# LED_PD_LKW_WH_3000030.net
KiCad netlist of a schematic drawn in Altium Designer
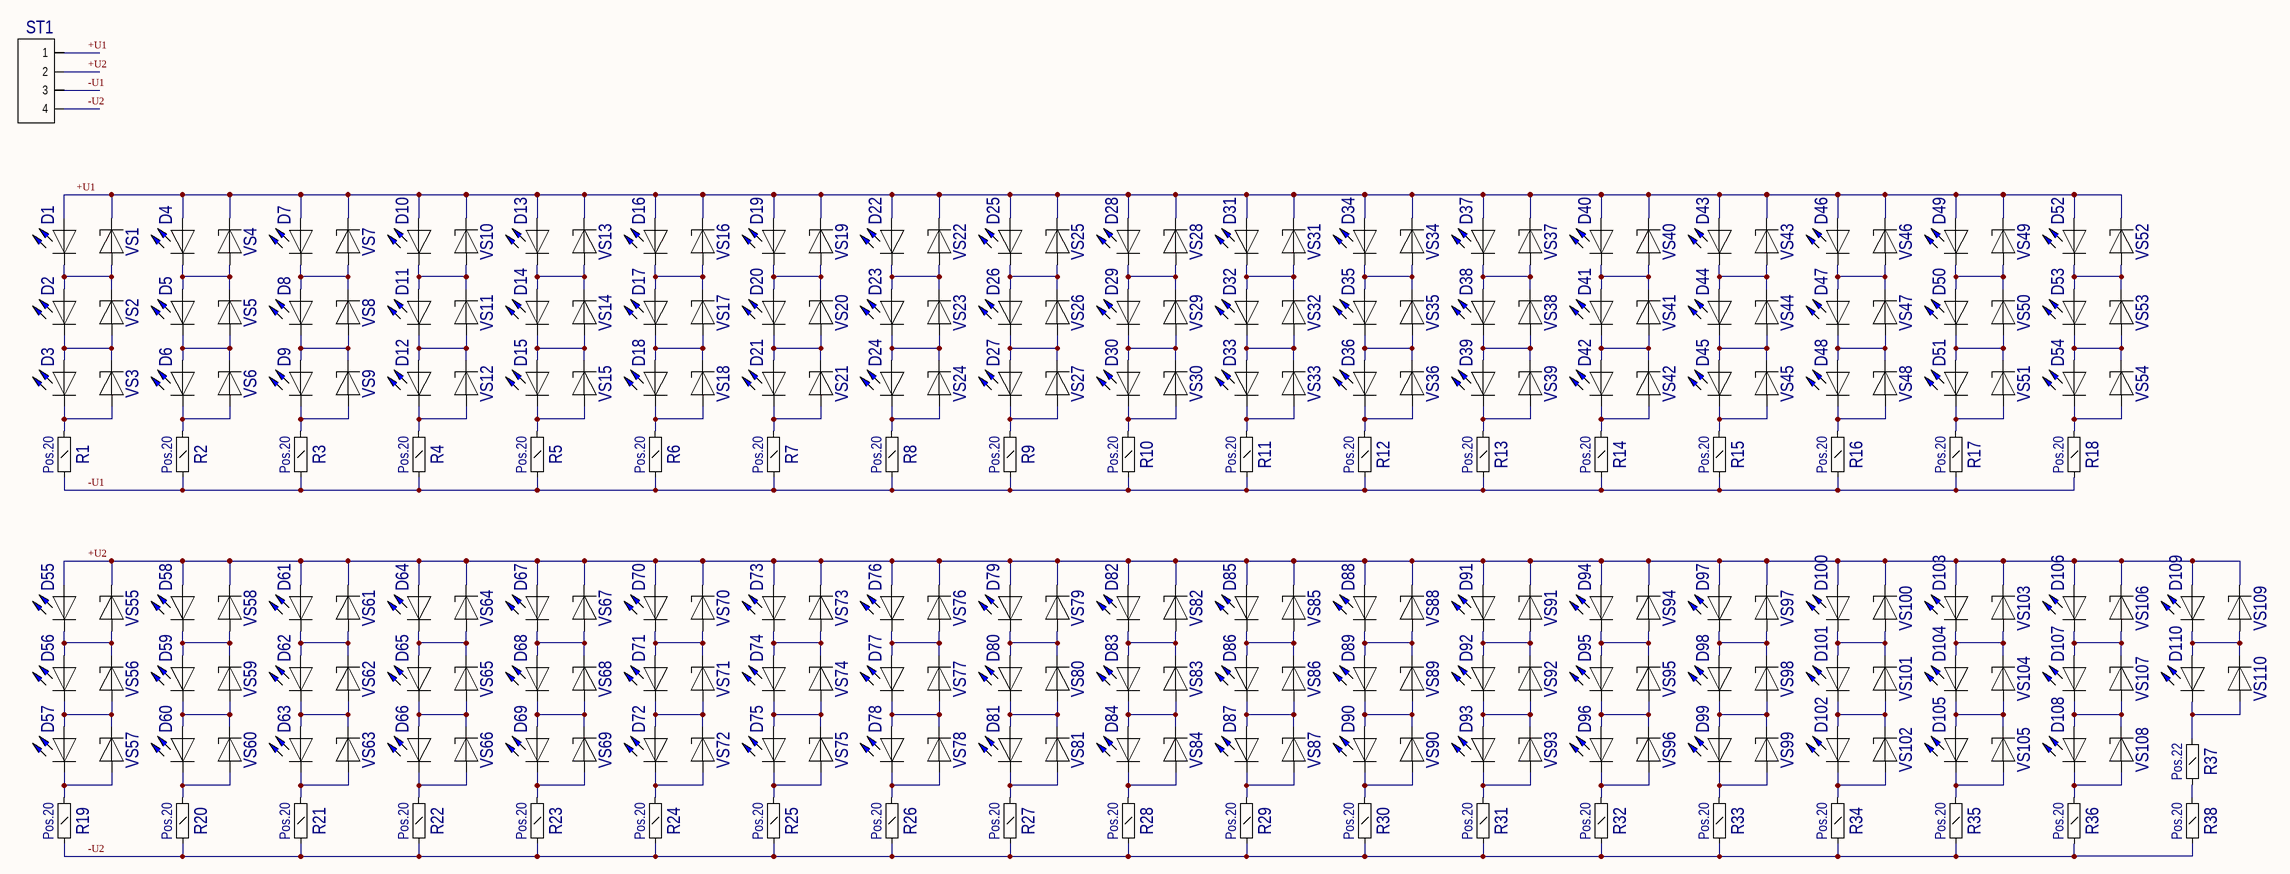
[diagram p0: LED PD LKW WH 3000030 (4F00221L_7P00491A).SchDoc]

(export (version "E")
  (design (tool "Eeschema 10.0.6"))
  (components
    (comp (ref "D1")
      (value "T66G_4")
      (footprint "T66G_4")
      (description "{Description}")
      (libsource (lib "30000137_3LED") (part "T66G_4"))
    )
    (comp (ref "D2")
      (value "T66G_4")
      (footprint "T66G_4")
      (description "{Description}")
      (libsource (lib "30000137_3LED") (part "T66G_4"))
    )
    (comp (ref "D3")
      (value "T66G_4")
      (footprint "T66G_4")
      (description "{Description}")
      (libsource (lib "30000137_3LED") (part "T66G_4"))
    )
    (comp (ref "D4")
      (value "T66G_4")
      (footprint "T66G_4")
      (description "{Description}")
      (libsource (lib "30000137_3LED") (part "T66G_4"))
    )
    (comp (ref "D5")
      (value "T66G_4")
      (footprint "T66G_4")
      (description "{Description}")
      (libsource (lib "30000137_3LED") (part "T66G_4"))
    )
    (comp (ref "D6")
      (value "T66G_4")
      (footprint "T66G_4")
      (description "{Description}")
      (libsource (lib "30000137_3LED") (part "T66G_4"))
    )
    (comp (ref "D7")
      (value "T66G_4")
      (footprint "T66G_4")
      (description "{Description}")
      (libsource (lib "30000137_3LED") (part "T66G_4"))
    )
    (comp (ref "D8")
      (value "T66G_4")
      (footprint "T66G_4")
      (description "{Description}")
      (libsource (lib "30000137_3LED") (part "T66G_4"))
    )
    (comp (ref "D9")
      (value "T66G_4")
      (footprint "T66G_4")
      (description "{Description}")
      (libsource (lib "30000137_3LED") (part "T66G_4"))
    )
    (comp (ref "D10")
      (value "T66G_4")
      (footprint "T66G_4")
      (description "{Description}")
      (libsource (lib "30000137_3LED") (part "T66G_4"))
    )
    (comp (ref "D11")
      (value "T66G_4")
      (footprint "T66G_4")
      (description "{Description}")
      (libsource (lib "30000137_3LED") (part "T66G_4"))
    )
    (comp (ref "D12")
      (value "T66G_4")
      (footprint "T66G_4")
      (description "{Description}")
      (libsource (lib "30000137_3LED") (part "T66G_4"))
    )
    (comp (ref "D13")
      (value "T66G_4")
      (footprint "T66G_4")
      (description "{Description}")
      (libsource (lib "30000137_3LED") (part "T66G_4"))
    )
    (comp (ref "D14")
      (value "T66G_4")
      (footprint "T66G_4")
      (description "{Description}")
      (libsource (lib "30000137_3LED") (part "T66G_4"))
    )
    (comp (ref "D15")
      (value "T66G_4")
      (footprint "T66G_4")
      (description "{Description}")
      (libsource (lib "30000137_3LED") (part "T66G_4"))
    )
    (comp (ref "D16")
      (value "T66G_4")
      (footprint "T66G_4")
      (description "{Description}")
      (libsource (lib "30000137_3LED") (part "T66G_4"))
    )
    (comp (ref "D17")
      (value "T66G_4")
      (footprint "T66G_4")
      (description "{Description}")
      (libsource (lib "30000137_3LED") (part "T66G_4"))
    )
    (comp (ref "D18")
      (value "T66G_4")
      (footprint "T66G_4")
      (description "{Description}")
      (libsource (lib "30000137_3LED") (part "T66G_4"))
    )
    (comp (ref "D19")
      (value "T66G_4")
      (footprint "T66G_4")
      (description "{Description}")
      (libsource (lib "30000137_3LED") (part "T66G_4"))
    )
    (comp (ref "D20")
      (value "T66G_4")
      (footprint "T66G_4")
      (description "{Description}")
      (libsource (lib "30000137_3LED") (part "T66G_4"))
    )
    (comp (ref "D21")
      (value "T66G_4")
      (footprint "T66G_4")
      (description "{Description}")
      (libsource (lib "30000137_3LED") (part "T66G_4"))
    )
    (comp (ref "D22")
      (value "T66G_4")
      (footprint "T66G_4")
      (description "{Description}")
      (libsource (lib "30000137_3LED") (part "T66G_4"))
    )
    (comp (ref "D23")
      (value "T66G_4")
      (footprint "T66G_4")
      (description "{Description}")
      (libsource (lib "30000137_3LED") (part "T66G_4"))
    )
    (comp (ref "D24")
      (value "T66G_4")
      (footprint "T66G_4")
      (description "{Description}")
      (libsource (lib "30000137_3LED") (part "T66G_4"))
    )
    (comp (ref "D25")
      (value "T66G_4")
      (footprint "T66G_4")
      (description "{Description}")
      (libsource (lib "30000137_3LED") (part "T66G_4"))
    )
    (comp (ref "D26")
      (value "T66G_4")
      (footprint "T66G_4")
      (description "{Description}")
      (libsource (lib "30000137_3LED") (part "T66G_4"))
    )
    (comp (ref "D27")
      (value "T66G_4")
      (footprint "T66G_4")
      (description "{Description}")
      (libsource (lib "30000137_3LED") (part "T66G_4"))
    )
    (comp (ref "D28")
      (value "T66G_4")
      (footprint "T66G_4")
      (description "{Description}")
      (libsource (lib "30000137_3LED") (part "T66G_4"))
    )
    (comp (ref "D29")
      (value "T66G_4")
      (footprint "T66G_4")
      (description "{Description}")
      (libsource (lib "30000137_3LED") (part "T66G_4"))
    )
    (comp (ref "D30")
      (value "T66G_4")
      (footprint "T66G_4")
      (description "{Description}")
      (libsource (lib "30000137_3LED") (part "T66G_4"))
    )
    (comp (ref "D31")
      (value "T66G_4")
      (footprint "T66G_4")
      (description "{Description}")
      (libsource (lib "30000137_3LED") (part "T66G_4"))
    )
    (comp (ref "D32")
      (value "T66G_4")
      (footprint "T66G_4")
      (description "{Description}")
      (libsource (lib "30000137_3LED") (part "T66G_4"))
    )
    (comp (ref "D33")
      (value "T66G_4")
      (footprint "T66G_4")
      (description "{Description}")
      (libsource (lib "30000137_3LED") (part "T66G_4"))
    )
    (comp (ref "D34")
      (value "T66G_4")
      (footprint "T66G_4")
      (description "{Description}")
      (libsource (lib "30000137_3LED") (part "T66G_4"))
    )
    (comp (ref "D35")
      (value "T66G_4")
      (footprint "T66G_4")
      (description "{Description}")
      (libsource (lib "30000137_3LED") (part "T66G_4"))
    )
    (comp (ref "D36")
      (value "T66G_4")
      (footprint "T66G_4")
      (description "{Description}")
      (libsource (lib "30000137_3LED") (part "T66G_4"))
    )
    (comp (ref "D37")
      (value "T66G_4")
      (footprint "T66G_4")
      (description "{Description}")
      (libsource (lib "30000137_3LED") (part "T66G_4"))
    )
    (comp (ref "D38")
      (value "T66G_4")
      (footprint "T66G_4")
      (description "{Description}")
      (libsource (lib "30000137_3LED") (part "T66G_4"))
    )
    (comp (ref "D39")
      (value "T66G_4")
      (footprint "T66G_4")
      (description "{Description}")
      (libsource (lib "30000137_3LED") (part "T66G_4"))
    )
    (comp (ref "D40")
      (value "T66G_4")
      (footprint "T66G_4")
      (description "{Description}")
      (libsource (lib "30000137_3LED") (part "T66G_4"))
    )
    (comp (ref "D41")
      (value "T66G_4")
      (footprint "T66G_4")
      (description "{Description}")
      (libsource (lib "30000137_3LED") (part "T66G_4"))
    )
    (comp (ref "D42")
      (value "T66G_4")
      (footprint "T66G_4")
      (description "{Description}")
      (libsource (lib "30000137_3LED") (part "T66G_4"))
    )
    (comp (ref "D43")
      (value "T66G_4")
      (footprint "T66G_4")
      (description "{Description}")
      (libsource (lib "30000137_3LED") (part "T66G_4"))
    )
    (comp (ref "D44")
      (value "T66G_4")
      (footprint "T66G_4")
      (description "{Description}")
      (libsource (lib "30000137_3LED") (part "T66G_4"))
    )
    (comp (ref "D45")
      (value "T66G_4")
      (footprint "T66G_4")
      (description "{Description}")
      (libsource (lib "30000137_3LED") (part "T66G_4"))
    )
    (comp (ref "D46")
      (value "T66G_4")
      (footprint "T66G_4")
      (description "{Description}")
      (libsource (lib "30000137_3LED") (part "T66G_4"))
    )
    (comp (ref "D47")
      (value "T66G_4")
      (footprint "T66G_4")
      (description "{Description}")
      (libsource (lib "30000137_3LED") (part "T66G_4"))
    )
    (comp (ref "D48")
      (value "T66G_4")
      (footprint "T66G_4")
      (description "{Description}")
      (libsource (lib "30000137_3LED") (part "T66G_4"))
    )
    (comp (ref "D49")
      (value "T66G_4")
      (footprint "T66G_4")
      (description "{Description}")
      (libsource (lib "30000137_3LED") (part "T66G_4"))
    )
    (comp (ref "D50")
      (value "T66G_4")
      (footprint "T66G_4")
      (description "{Description}")
      (libsource (lib "30000137_3LED") (part "T66G_4"))
    )
    (comp (ref "D51")
      (value "T66G_4")
      (footprint "T66G_4")
      (description "{Description}")
      (libsource (lib "30000137_3LED") (part "T66G_4"))
    )
    (comp (ref "D52")
      (value "T66G_4")
      (footprint "T66G_4")
      (description "{Description}")
      (libsource (lib "30000137_3LED") (part "T66G_4"))
    )
    (comp (ref "D53")
      (value "T66G_4")
      (footprint "T66G_4")
      (description "{Description}")
      (libsource (lib "30000137_3LED") (part "T66G_4"))
    )
    (comp (ref "D54")
      (value "T66G_4")
      (footprint "T66G_4")
      (description "{Description}")
      (libsource (lib "30000137_3LED") (part "T66G_4"))
    )
    (comp (ref "D55")
      (value "T66G_4")
      (footprint "T66G_4")
      (description "{Description}")
      (libsource (lib "30000137_3LED") (part "T66G_4"))
    )
    (comp (ref "D56")
      (value "T66G_4")
      (footprint "T66G_4")
      (description "{Description}")
      (libsource (lib "30000137_3LED") (part "T66G_4"))
    )
    (comp (ref "D57")
      (value "T66G_4")
      (footprint "T66G_4")
      (description "{Description}")
      (libsource (lib "30000137_3LED") (part "T66G_4"))
    )
    (comp (ref "D58")
      (value "T66G_4")
      (footprint "T66G_4")
      (description "{Description}")
      (libsource (lib "30000137_3LED") (part "T66G_4"))
    )
    (comp (ref "D59")
      (value "T66G_4")
      (footprint "T66G_4")
      (description "{Description}")
      (libsource (lib "30000137_3LED") (part "T66G_4"))
    )
    (comp (ref "D60")
      (value "T66G_4")
      (footprint "T66G_4")
      (description "{Description}")
      (libsource (lib "30000137_3LED") (part "T66G_4"))
    )
    (comp (ref "D61")
      (value "T66G_4")
      (footprint "T66G_4")
      (description "{Description}")
      (libsource (lib "30000137_3LED") (part "T66G_4"))
    )
    (comp (ref "D62")
      (value "T66G_4")
      (footprint "T66G_4")
      (description "{Description}")
      (libsource (lib "30000137_3LED") (part "T66G_4"))
    )
    (comp (ref "D63")
      (value "T66G_4")
      (footprint "T66G_4")
      (description "{Description}")
      (libsource (lib "30000137_3LED") (part "T66G_4"))
    )
    (comp (ref "D64")
      (value "T66G_4")
      (footprint "T66G_4")
      (description "{Description}")
      (libsource (lib "30000137_3LED") (part "T66G_4"))
    )
    (comp (ref "D65")
      (value "T66G_4")
      (footprint "T66G_4")
      (description "{Description}")
      (libsource (lib "30000137_3LED") (part "T66G_4"))
    )
    (comp (ref "D66")
      (value "T66G_4")
      (footprint "T66G_4")
      (description "{Description}")
      (libsource (lib "30000137_3LED") (part "T66G_4"))
    )
    (comp (ref "D67")
      (value "T66G_4")
      (footprint "T66G_4")
      (description "{Description}")
      (libsource (lib "30000137_3LED") (part "T66G_4"))
    )
    (comp (ref "D68")
      (value "T66G_4")
      (footprint "T66G_4")
      (description "{Description}")
      (libsource (lib "30000137_3LED") (part "T66G_4"))
    )
    (comp (ref "D69")
      (value "T66G_4")
      (footprint "T66G_4")
      (description "{Description}")
      (libsource (lib "30000137_3LED") (part "T66G_4"))
    )
    (comp (ref "D70")
      (value "T66G_4")
      (footprint "T66G_4")
      (description "{Description}")
      (libsource (lib "30000137_3LED") (part "T66G_4"))
    )
    (comp (ref "D71")
      (value "T66G_4")
      (footprint "T66G_4")
      (description "{Description}")
      (libsource (lib "30000137_3LED") (part "T66G_4"))
    )
    (comp (ref "D72")
      (value "T66G_4")
      (footprint "T66G_4")
      (description "{Description}")
      (libsource (lib "30000137_3LED") (part "T66G_4"))
    )
    (comp (ref "D73")
      (value "T66G_4")
      (footprint "T66G_4")
      (description "{Description}")
      (libsource (lib "30000137_3LED") (part "T66G_4"))
    )
    (comp (ref "D74")
      (value "T66G_4")
      (footprint "T66G_4")
      (description "{Description}")
      (libsource (lib "30000137_3LED") (part "T66G_4"))
    )
    (comp (ref "D75")
      (value "T66G_4")
      (footprint "T66G_4")
      (description "{Description}")
      (libsource (lib "30000137_3LED") (part "T66G_4"))
    )
    (comp (ref "D76")
      (value "T66G_4")
      (footprint "T66G_4")
      (description "{Description}")
      (libsource (lib "30000137_3LED") (part "T66G_4"))
    )
    (comp (ref "D77")
      (value "T66G_4")
      (footprint "T66G_4")
      (description "{Description}")
      (libsource (lib "30000137_3LED") (part "T66G_4"))
    )
    (comp (ref "D78")
      (value "T66G_4")
      (footprint "T66G_4")
      (description "{Description}")
      (libsource (lib "30000137_3LED") (part "T66G_4"))
    )
    (comp (ref "D79")
      (value "T66G_4")
      (footprint "T66G_4")
      (description "{Description}")
      (libsource (lib "30000137_3LED") (part "T66G_4"))
    )
    (comp (ref "D80")
      (value "T66G_4")
      (footprint "T66G_4")
      (description "{Description}")
      (libsource (lib "30000137_3LED") (part "T66G_4"))
    )
    (comp (ref "D81")
      (value "T66G_4")
      (footprint "T66G_4")
      (description "{Description}")
      (libsource (lib "30000137_3LED") (part "T66G_4"))
    )
    (comp (ref "D82")
      (value "T66G_4")
      (footprint "T66G_4")
      (description "{Description}")
      (libsource (lib "30000137_3LED") (part "T66G_4"))
    )
    (comp (ref "D83")
      (value "T66G_4")
      (footprint "T66G_4")
      (description "{Description}")
      (libsource (lib "30000137_3LED") (part "T66G_4"))
    )
    (comp (ref "D84")
      (value "T66G_4")
      (footprint "T66G_4")
      (description "{Description}")
      (libsource (lib "30000137_3LED") (part "T66G_4"))
    )
    (comp (ref "D85")
      (value "T66G_4")
      (footprint "T66G_4")
      (description "{Description}")
      (libsource (lib "30000137_3LED") (part "T66G_4"))
    )
    (comp (ref "D86")
      (value "T66G_4")
      (footprint "T66G_4")
      (description "{Description}")
      (libsource (lib "30000137_3LED") (part "T66G_4"))
    )
    (comp (ref "D87")
      (value "T66G_4")
      (footprint "T66G_4")
      (description "{Description}")
      (libsource (lib "30000137_3LED") (part "T66G_4"))
    )
    (comp (ref "D88")
      (value "T66G_4")
      (footprint "T66G_4")
      (description "{Description}")
      (libsource (lib "30000137_3LED") (part "T66G_4"))
    )
    (comp (ref "D89")
      (value "T66G_4")
      (footprint "T66G_4")
      (description "{Description}")
      (libsource (lib "30000137_3LED") (part "T66G_4"))
    )
    (comp (ref "D90")
      (value "T66G_4")
      (footprint "T66G_4")
      (description "{Description}")
      (libsource (lib "30000137_3LED") (part "T66G_4"))
    )
    (comp (ref "D91")
      (value "T66G_4")
      (footprint "T66G_4")
      (description "{Description}")
      (libsource (lib "30000137_3LED") (part "T66G_4"))
    )
    (comp (ref "D92")
      (value "T66G_4")
      (footprint "T66G_4")
      (description "{Description}")
      (libsource (lib "30000137_3LED") (part "T66G_4"))
    )
    (comp (ref "D93")
      (value "T66G_4")
      (footprint "T66G_4")
      (description "{Description}")
      (libsource (lib "30000137_3LED") (part "T66G_4"))
    )
    (comp (ref "D94")
      (value "T66G_4")
      (footprint "T66G_4")
      (description "{Description}")
      (libsource (lib "30000137_3LED") (part "T66G_4"))
    )
    (comp (ref "D95")
      (value "T66G_4")
      (footprint "T66G_4")
      (description "{Description}")
      (libsource (lib "30000137_3LED") (part "T66G_4"))
    )
    (comp (ref "D96")
      (value "T66G_4")
      (footprint "T66G_4")
      (description "{Description}")
      (libsource (lib "30000137_3LED") (part "T66G_4"))
    )
    (comp (ref "D97")
      (value "T66G_4")
      (footprint "T66G_4")
      (description "{Description}")
      (libsource (lib "30000137_3LED") (part "T66G_4"))
    )
    (comp (ref "D98")
      (value "T66G_4")
      (footprint "T66G_4")
      (description "{Description}")
      (libsource (lib "30000137_3LED") (part "T66G_4"))
    )
    (comp (ref "D99")
      (value "T66G_4")
      (footprint "T66G_4")
      (description "{Description}")
      (libsource (lib "30000137_3LED") (part "T66G_4"))
    )
    (comp (ref "D100")
      (value "T66G_4")
      (footprint "T66G_4")
      (description "{Description}")
      (libsource (lib "30000137_3LED") (part "T66G_4"))
    )
    (comp (ref "D101")
      (value "T66G_4")
      (footprint "T66G_4")
      (description "{Description}")
      (libsource (lib "30000137_3LED") (part "T66G_4"))
    )
    (comp (ref "D102")
      (value "T66G_4")
      (footprint "T66G_4")
      (description "{Description}")
      (libsource (lib "30000137_3LED") (part "T66G_4"))
    )
    (comp (ref "D103")
      (value "T66G_4")
      (footprint "T66G_4")
      (description "{Description}")
      (libsource (lib "30000137_3LED") (part "T66G_4"))
    )
    (comp (ref "D104")
      (value "T66G_4")
      (footprint "T66G_4")
      (description "{Description}")
      (libsource (lib "30000137_3LED") (part "T66G_4"))
    )
    (comp (ref "D105")
      (value "T66G_4")
      (footprint "T66G_4")
      (description "{Description}")
      (libsource (lib "30000137_3LED") (part "T66G_4"))
    )
    (comp (ref "D106")
      (value "T66G_4")
      (footprint "T66G_4")
      (description "{Description}")
      (libsource (lib "30000137_3LED") (part "T66G_4"))
    )
    (comp (ref "D107")
      (value "T66G_4")
      (footprint "T66G_4")
      (description "{Description}")
      (libsource (lib "30000137_3LED") (part "T66G_4"))
    )
    (comp (ref "D108")
      (value "T66G_4")
      (footprint "T66G_4")
      (description "{Description}")
      (libsource (lib "30000137_3LED") (part "T66G_4"))
    )
    (comp (ref "D109")
      (value "T66G_4")
      (footprint "T66G_4")
      (description "{Description}")
      (libsource (lib "30000137_3LED") (part "T66G_4"))
    )
    (comp (ref "D110")
      (value "T66G_4")
      (footprint "T66G_4")
      (description "{Description}")
      (libsource (lib "30000137_3LED") (part "T66G_4"))
    )
    (comp (ref "R1")
      (value "Pos.20")
      (footprint "RC1206S")
      (description "R1206S")
      (libsource (lib "30000137_3LED") (part "R1206S"))
    )
    (comp (ref "R2")
      (value "Pos.20")
      (footprint "RC1206S")
      (description "R1206S")
      (libsource (lib "30000137_3LED") (part "R1206S"))
    )
    (comp (ref "R3")
      (value "Pos.20")
      (footprint "RC1206S")
      (description "R1206S")
      (libsource (lib "30000137_3LED") (part "R1206S"))
    )
    (comp (ref "R4")
      (value "Pos.20")
      (footprint "RC1206S")
      (description "R1206S")
      (libsource (lib "30000137_3LED") (part "R1206S"))
    )
    (comp (ref "R5")
      (value "Pos.20")
      (footprint "RC1206S")
      (description "R1206S")
      (libsource (lib "30000137_3LED") (part "R1206S"))
    )
    (comp (ref "R6")
      (value "Pos.20")
      (footprint "RC1206S")
      (description "R1206S")
      (libsource (lib "30000137_3LED") (part "R1206S"))
    )
    (comp (ref "R7")
      (value "Pos.20")
      (footprint "RC1206S")
      (description "R1206S")
      (libsource (lib "30000137_3LED") (part "R1206S"))
    )
    (comp (ref "R8")
      (value "Pos.20")
      (footprint "RC1206S")
      (description "R1206S")
      (libsource (lib "30000137_3LED") (part "R1206S"))
    )
    (comp (ref "R9")
      (value "Pos.20")
      (footprint "RC1206S")
      (description "R1206S")
      (libsource (lib "30000137_3LED") (part "R1206S"))
    )
    (comp (ref "R10")
      (value "Pos.20")
      (footprint "RC1206S")
      (description "R1206S")
      (libsource (lib "30000137_3LED") (part "R1206S"))
    )
    (comp (ref "R11")
      (value "Pos.20")
      (footprint "RC1206S")
      (description "R1206S")
      (libsource (lib "30000137_3LED") (part "R1206S"))
    )
    (comp (ref "R12")
      (value "Pos.20")
      (footprint "RC1206S")
      (description "R1206S")
      (libsource (lib "30000137_3LED") (part "R1206S"))
    )
    (comp (ref "R13")
      (value "Pos.20")
      (footprint "RC1206S")
      (description "R1206S")
      (libsource (lib "30000137_3LED") (part "R1206S"))
    )
    (comp (ref "R14")
      (value "Pos.20")
      (footprint "RC1206S")
      (description "R1206S")
      (libsource (lib "30000137_3LED") (part "R1206S"))
    )
    (comp (ref "R15")
      (value "Pos.20")
      (footprint "RC1206S")
      (description "R1206S")
      (libsource (lib "30000137_3LED") (part "R1206S"))
    )
    (comp (ref "R16")
      (value "Pos.20")
      (footprint "RC1206S")
      (description "R1206S")
      (libsource (lib "30000137_3LED") (part "R1206S"))
    )
    (comp (ref "R17")
      (value "Pos.20")
      (footprint "RC1206S")
      (description "R1206S")
      (libsource (lib "30000137_3LED") (part "R1206S"))
    )
    (comp (ref "R18")
      (value "Pos.20")
      (footprint "RC1206S")
      (description "R1206S")
      (libsource (lib "30000137_3LED") (part "R1206S"))
    )
    (comp (ref "R19")
      (value "Pos.20")
      (footprint "RC1206S")
      (description "R1206S")
      (libsource (lib "30000137_3LED") (part "R1206S"))
    )
    (comp (ref "R20")
      (value "Pos.20")
      (footprint "RC1206S")
      (description "R1206S")
      (libsource (lib "30000137_3LED") (part "R1206S"))
    )
    (comp (ref "R21")
      (value "Pos.20")
      (footprint "RC1206S")
      (description "R1206S")
      (libsource (lib "30000137_3LED") (part "R1206S"))
    )
    (comp (ref "R22")
      (value "Pos.20")
      (footprint "RC1206S")
      (description "R1206S")
      (libsource (lib "30000137_3LED") (part "R1206S"))
    )
    (comp (ref "R23")
      (value "Pos.20")
      (footprint "RC1206S")
      (description "R1206S")
      (libsource (lib "30000137_3LED") (part "R1206S"))
    )
    (comp (ref "R24")
      (value "Pos.20")
      (footprint "RC1206S")
      (description "R1206S")
      (libsource (lib "30000137_3LED") (part "R1206S"))
    )
    (comp (ref "R25")
      (value "Pos.20")
      (footprint "RC1206S")
      (description "R1206S")
      (libsource (lib "30000137_3LED") (part "R1206S"))
    )
    (comp (ref "R26")
      (value "Pos.20")
      (footprint "RC1206S")
      (description "R1206S")
      (libsource (lib "30000137_3LED") (part "R1206S"))
    )
    (comp (ref "R27")
      (value "Pos.20")
      (footprint "RC1206S")
      (description "R1206S")
      (libsource (lib "30000137_3LED") (part "R1206S"))
    )
    (comp (ref "R28")
      (value "Pos.20")
      (footprint "RC1206S")
      (description "R1206S")
      (libsource (lib "30000137_3LED") (part "R1206S"))
    )
    (comp (ref "R29")
      (value "Pos.20")
      (footprint "RC1206S")
      (description "R1206S")
      (libsource (lib "30000137_3LED") (part "R1206S"))
    )
    (comp (ref "R30")
      (value "Pos.20")
      (footprint "RC1206S")
      (description "R1206S")
      (libsource (lib "30000137_3LED") (part "R1206S"))
    )
    (comp (ref "R31")
      (value "Pos.20")
      (footprint "RC1206S")
      (description "R1206S")
      (libsource (lib "30000137_3LED") (part "R1206S"))
    )
    (comp (ref "R32")
      (value "Pos.20")
      (footprint "RC1206S")
      (description "R1206S")
      (libsource (lib "30000137_3LED") (part "R1206S"))
    )
    (comp (ref "R33")
      (value "Pos.20")
      (footprint "RC1206S")
      (description "R1206S")
      (libsource (lib "30000137_3LED") (part "R1206S"))
    )
    (comp (ref "R34")
      (value "Pos.20")
      (footprint "RC1206S")
      (description "R1206S")
      (libsource (lib "30000137_3LED") (part "R1206S"))
    )
    (comp (ref "R35")
      (value "Pos.20")
      (footprint "RC1206S")
      (description "R1206S")
      (libsource (lib "30000137_3LED") (part "R1206S"))
    )
    (comp (ref "R36")
      (value "Pos.20")
      (footprint "RC1206S")
      (description "R1206S")
      (libsource (lib "30000137_3LED") (part "R1206S"))
    )
    (comp (ref "R37")
      (value "Pos.22")
      (footprint "RC1206S")
      (description "R1206S")
      (libsource (lib "30000137_3LED") (part "R1206S_1"))
    )
    (comp (ref "R38")
      (value "Pos.20")
      (footprint "RC1206S")
      (description "R1206S")
      (libsource (lib "30000137_3LED") (part "R1206S"))
    )
    (comp (ref "ST1") (value "BAND4") (footprint "BAND4") (libsource (lib "30000137_3LED") (part "BAND4")))
    (comp (ref "VS1") (value "BZX84") (footprint "SOT23") (libsource (lib "30000137_3LED") (part "BZX84")))
    (comp (ref "VS2") (value "BZX84") (footprint "SOT23") (libsource (lib "30000137_3LED") (part "BZX84")))
    (comp (ref "VS3") (value "BZX84") (footprint "SOT23") (libsource (lib "30000137_3LED") (part "BZX84")))
    (comp (ref "VS4") (value "BZX84") (footprint "SOT23") (libsource (lib "30000137_3LED") (part "BZX84")))
    (comp (ref "VS5") (value "BZX84") (footprint "SOT23") (libsource (lib "30000137_3LED") (part "BZX84")))
    (comp (ref "VS6") (value "BZX84") (footprint "SOT23") (libsource (lib "30000137_3LED") (part "BZX84")))
    (comp (ref "VS7") (value "BZX84") (footprint "SOT23") (libsource (lib "30000137_3LED") (part "BZX84")))
    (comp (ref "VS8") (value "BZX84") (footprint "SOT23") (libsource (lib "30000137_3LED") (part "BZX84")))
    (comp (ref "VS9") (value "BZX84") (footprint "SOT23") (libsource (lib "30000137_3LED") (part "BZX84")))
    (comp (ref "VS10") (value "BZX84") (footprint "SOT23") (libsource (lib "30000137_3LED") (part "BZX84")))
    (comp (ref "VS11") (value "BZX84") (footprint "SOT23") (libsource (lib "30000137_3LED") (part "BZX84")))
    (comp (ref "VS12") (value "BZX84") (footprint "SOT23") (libsource (lib "30000137_3LED") (part "BZX84")))
    (comp (ref "VS13") (value "BZX84") (footprint "SOT23") (libsource (lib "30000137_3LED") (part "BZX84")))
    (comp (ref "VS14") (value "BZX84") (footprint "SOT23") (libsource (lib "30000137_3LED") (part "BZX84")))
    (comp (ref "VS15") (value "BZX84") (footprint "SOT23") (libsource (lib "30000137_3LED") (part "BZX84")))
    (comp (ref "VS16") (value "BZX84") (footprint "SOT23") (libsource (lib "30000137_3LED") (part "BZX84")))
    (comp (ref "VS17") (value "BZX84") (footprint "SOT23") (libsource (lib "30000137_3LED") (part "BZX84")))
    (comp (ref "VS18") (value "BZX84") (footprint "SOT23") (libsource (lib "30000137_3LED") (part "BZX84")))
    (comp (ref "VS19") (value "BZX84") (footprint "SOT23") (libsource (lib "30000137_3LED") (part "BZX84")))
    (comp (ref "VS20") (value "BZX84") (footprint "SOT23") (libsource (lib "30000137_3LED") (part "BZX84")))
    (comp (ref "VS21") (value "BZX84") (footprint "SOT23") (libsource (lib "30000137_3LED") (part "BZX84")))
    (comp (ref "VS22") (value "BZX84") (footprint "SOT23") (libsource (lib "30000137_3LED") (part "BZX84")))
    (comp (ref "VS23") (value "BZX84") (footprint "SOT23") (libsource (lib "30000137_3LED") (part "BZX84")))
    (comp (ref "VS24") (value "BZX84") (footprint "SOT23") (libsource (lib "30000137_3LED") (part "BZX84")))
    (comp (ref "VS25") (value "BZX84") (footprint "SOT23") (libsource (lib "30000137_3LED") (part "BZX84")))
    (comp (ref "VS26") (value "BZX84") (footprint "SOT23") (libsource (lib "30000137_3LED") (part "BZX84")))
    (comp (ref "VS27") (value "BZX84") (footprint "SOT23") (libsource (lib "30000137_3LED") (part "BZX84")))
    (comp (ref "VS28") (value "BZX84") (footprint "SOT23") (libsource (lib "30000137_3LED") (part "BZX84")))
    (comp (ref "VS29") (value "BZX84") (footprint "SOT23") (libsource (lib "30000137_3LED") (part "BZX84")))
    (comp (ref "VS30") (value "BZX84") (footprint "SOT23") (libsource (lib "30000137_3LED") (part "BZX84")))
    (comp (ref "VS31") (value "BZX84") (footprint "SOT23") (libsource (lib "30000137_3LED") (part "BZX84")))
    (comp (ref "VS32") (value "BZX84") (footprint "SOT23") (libsource (lib "30000137_3LED") (part "BZX84")))
    (comp (ref "VS33") (value "BZX84") (footprint "SOT23") (libsource (lib "30000137_3LED") (part "BZX84")))
    (comp (ref "VS34") (value "BZX84") (footprint "SOT23") (libsource (lib "30000137_3LED") (part "BZX84")))
    (comp (ref "VS35") (value "BZX84") (footprint "SOT23") (libsource (lib "30000137_3LED") (part "BZX84")))
    (comp (ref "VS36") (value "BZX84") (footprint "SOT23") (libsource (lib "30000137_3LED") (part "BZX84")))
    (comp (ref "VS37") (value "BZX84") (footprint "SOT23") (libsource (lib "30000137_3LED") (part "BZX84")))
    (comp (ref "VS38") (value "BZX84") (footprint "SOT23") (libsource (lib "30000137_3LED") (part "BZX84")))
    (comp (ref "VS39") (value "BZX84") (footprint "SOT23") (libsource (lib "30000137_3LED") (part "BZX84")))
    (comp (ref "VS40") (value "BZX84") (footprint "SOT23") (libsource (lib "30000137_3LED") (part "BZX84")))
    (comp (ref "VS41") (value "BZX84") (footprint "SOT23") (libsource (lib "30000137_3LED") (part "BZX84")))
    (comp (ref "VS42") (value "BZX84") (footprint "SOT23") (libsource (lib "30000137_3LED") (part "BZX84")))
    (comp (ref "VS43") (value "BZX84") (footprint "SOT23") (libsource (lib "30000137_3LED") (part "BZX84")))
    (comp (ref "VS44") (value "BZX84") (footprint "SOT23") (libsource (lib "30000137_3LED") (part "BZX84")))
    (comp (ref "VS45") (value "BZX84") (footprint "SOT23") (libsource (lib "30000137_3LED") (part "BZX84")))
    (comp (ref "VS46") (value "BZX84") (footprint "SOT23") (libsource (lib "30000137_3LED") (part "BZX84")))
    (comp (ref "VS47") (value "BZX84") (footprint "SOT23") (libsource (lib "30000137_3LED") (part "BZX84")))
    (comp (ref "VS48") (value "BZX84") (footprint "SOT23") (libsource (lib "30000137_3LED") (part "BZX84")))
    (comp (ref "VS49") (value "BZX84") (footprint "SOT23") (libsource (lib "30000137_3LED") (part "BZX84")))
    (comp (ref "VS50") (value "BZX84") (footprint "SOT23") (libsource (lib "30000137_3LED") (part "BZX84")))
    (comp (ref "VS51") (value "BZX84") (footprint "SOT23") (libsource (lib "30000137_3LED") (part "BZX84")))
    (comp (ref "VS52") (value "BZX84") (footprint "SOT23") (libsource (lib "30000137_3LED") (part "BZX84")))
    (comp (ref "VS53") (value "BZX84") (footprint "SOT23") (libsource (lib "30000137_3LED") (part "BZX84")))
    (comp (ref "VS54") (value "BZX84") (footprint "SOT23") (libsource (lib "30000137_3LED") (part "BZX84")))
    (comp (ref "VS55") (value "BZX84") (footprint "SOT23") (libsource (lib "30000137_3LED") (part "BZX84")))
    (comp (ref "VS56") (value "BZX84") (footprint "SOT23") (libsource (lib "30000137_3LED") (part "BZX84")))
    (comp (ref "VS57") (value "BZX84") (footprint "SOT23") (libsource (lib "30000137_3LED") (part "BZX84")))
    (comp (ref "VS58") (value "BZX84") (footprint "SOT23") (libsource (lib "30000137_3LED") (part "BZX84")))
    (comp (ref "VS59") (value "BZX84") (footprint "SOT23") (libsource (lib "30000137_3LED") (part "BZX84")))
    (comp (ref "VS60") (value "BZX84") (footprint "SOT23") (libsource (lib "30000137_3LED") (part "BZX84")))
    (comp (ref "VS61") (value "BZX84") (footprint "SOT23") (libsource (lib "30000137_3LED") (part "BZX84")))
    (comp (ref "VS62") (value "BZX84") (footprint "SOT23") (libsource (lib "30000137_3LED") (part "BZX84")))
    (comp (ref "VS63") (value "BZX84") (footprint "SOT23") (libsource (lib "30000137_3LED") (part "BZX84")))
    (comp (ref "VS64") (value "BZX84") (footprint "SOT23") (libsource (lib "30000137_3LED") (part "BZX84")))
    (comp (ref "VS65") (value "BZX84") (footprint "SOT23") (libsource (lib "30000137_3LED") (part "BZX84")))
    (comp (ref "VS66") (value "BZX84") (footprint "SOT23") (libsource (lib "30000137_3LED") (part "BZX84")))
    (comp (ref "VS67") (value "BZX84") (footprint "SOT23") (libsource (lib "30000137_3LED") (part "BZX84")))
    (comp (ref "VS68") (value "BZX84") (footprint "SOT23") (libsource (lib "30000137_3LED") (part "BZX84")))
    (comp (ref "VS69") (value "BZX84") (footprint "SOT23") (libsource (lib "30000137_3LED") (part "BZX84")))
    (comp (ref "VS70") (value "BZX84") (footprint "SOT23") (libsource (lib "30000137_3LED") (part "BZX84")))
    (comp (ref "VS71") (value "BZX84") (footprint "SOT23") (libsource (lib "30000137_3LED") (part "BZX84")))
    (comp (ref "VS72") (value "BZX84") (footprint "SOT23") (libsource (lib "30000137_3LED") (part "BZX84")))
    (comp (ref "VS73") (value "BZX84") (footprint "SOT23") (libsource (lib "30000137_3LED") (part "BZX84")))
    (comp (ref "VS74") (value "BZX84") (footprint "SOT23") (libsource (lib "30000137_3LED") (part "BZX84")))
    (comp (ref "VS75") (value "BZX84") (footprint "SOT23") (libsource (lib "30000137_3LED") (part "BZX84")))
    (comp (ref "VS76") (value "BZX84") (footprint "SOT23") (libsource (lib "30000137_3LED") (part "BZX84")))
    (comp (ref "VS77") (value "BZX84") (footprint "SOT23") (libsource (lib "30000137_3LED") (part "BZX84")))
    (comp (ref "VS78") (value "BZX84") (footprint "SOT23") (libsource (lib "30000137_3LED") (part "BZX84")))
    (comp (ref "VS79") (value "BZX84") (footprint "SOT23") (libsource (lib "30000137_3LED") (part "BZX84")))
    (comp (ref "VS80") (value "BZX84") (footprint "SOT23") (libsource (lib "30000137_3LED") (part "BZX84")))
    (comp (ref "VS81") (value "BZX84") (footprint "SOT23") (libsource (lib "30000137_3LED") (part "BZX84")))
    (comp (ref "VS82") (value "BZX84") (footprint "SOT23") (libsource (lib "30000137_3LED") (part "BZX84")))
    (comp (ref "VS83") (value "BZX84") (footprint "SOT23") (libsource (lib "30000137_3LED") (part "BZX84")))
    (comp (ref "VS84") (value "BZX84") (footprint "SOT23") (libsource (lib "30000137_3LED") (part "BZX84")))
    (comp (ref "VS85") (value "BZX84") (footprint "SOT23") (libsource (lib "30000137_3LED") (part "BZX84")))
    (comp (ref "VS86") (value "BZX84") (footprint "SOT23") (libsource (lib "30000137_3LED") (part "BZX84")))
    (comp (ref "VS87") (value "BZX84") (footprint "SOT23") (libsource (lib "30000137_3LED") (part "BZX84")))
    (comp (ref "VS88") (value "BZX84") (footprint "SOT23") (libsource (lib "30000137_3LED") (part "BZX84")))
    (comp (ref "VS89") (value "BZX84") (footprint "SOT23") (libsource (lib "30000137_3LED") (part "BZX84")))
    (comp (ref "VS90") (value "BZX84") (footprint "SOT23") (libsource (lib "30000137_3LED") (part "BZX84")))
    (comp (ref "VS91") (value "BZX84") (footprint "SOT23") (libsource (lib "30000137_3LED") (part "BZX84")))
    (comp (ref "VS92") (value "BZX84") (footprint "SOT23") (libsource (lib "30000137_3LED") (part "BZX84")))
    (comp (ref "VS93") (value "BZX84") (footprint "SOT23") (libsource (lib "30000137_3LED") (part "BZX84")))
    (comp (ref "VS94") (value "BZX84") (footprint "SOT23") (libsource (lib "30000137_3LED") (part "BZX84")))
    (comp (ref "VS95") (value "BZX84") (footprint "SOT23") (libsource (lib "30000137_3LED") (part "BZX84")))
    (comp (ref "VS96") (value "BZX84") (footprint "SOT23") (libsource (lib "30000137_3LED") (part "BZX84")))
    (comp (ref "VS97") (value "BZX84") (footprint "SOT23") (libsource (lib "30000137_3LED") (part "BZX84")))
    (comp (ref "VS98") (value "BZX84") (footprint "SOT23") (libsource (lib "30000137_3LED") (part "BZX84")))
    (comp (ref "VS99") (value "BZX84") (footprint "SOT23") (libsource (lib "30000137_3LED") (part "BZX84")))
    (comp (ref "VS100") (value "BZX84") (footprint "SOT23") (libsource (lib "30000137_3LED") (part "BZX84")))
    (comp (ref "VS101") (value "BZX84") (footprint "SOT23") (libsource (lib "30000137_3LED") (part "BZX84")))
    (comp (ref "VS102") (value "BZX84") (footprint "SOT23") (libsource (lib "30000137_3LED") (part "BZX84")))
    (comp (ref "VS103") (value "BZX84") (footprint "SOT23") (libsource (lib "30000137_3LED") (part "BZX84")))
    (comp (ref "VS104") (value "BZX84") (footprint "SOT23") (libsource (lib "30000137_3LED") (part "BZX84")))
    (comp (ref "VS105") (value "BZX84") (footprint "SOT23") (libsource (lib "30000137_3LED") (part "BZX84")))
    (comp (ref "VS106") (value "BZX84") (footprint "SOT23") (libsource (lib "30000137_3LED") (part "BZX84")))
    (comp (ref "VS107") (value "BZX84") (footprint "SOT23") (libsource (lib "30000137_3LED") (part "BZX84")))
    (comp (ref "VS108") (value "BZX84") (footprint "SOT23") (libsource (lib "30000137_3LED") (part "BZX84")))
    (comp (ref "VS109") (value "BZX84") (footprint "SOT23") (libsource (lib "30000137_3LED") (part "BZX84")))
    (comp (ref "VS110") (value "BZX84") (footprint "SOT23") (libsource (lib "30000137_3LED") (part "BZX84")))
  )
  (nets
    (net (code "1") (name "/+U1") (class "Default")
      (node (ref "D1") (pin "2") (pinfunction "A_2") (pintype "passive"))
      (node (ref "D10") (pin "2") (pinfunction "A_2") (pintype "passive"))
      (node (ref "D13") (pin "2") (pinfunction "A_2") (pintype "passive"))
      (node (ref "D16") (pin "2") (pinfunction "A_2") (pintype "passive"))
      (node (ref "D19") (pin "2") (pinfunction "A_2") (pintype "passive"))
      (node (ref "D22") (pin "2") (pinfunction "A_2") (pintype "passive"))
      (node (ref "D25") (pin "2") (pinfunction "A_2") (pintype "passive"))
      (node (ref "D28") (pin "2") (pinfunction "A_2") (pintype "passive"))
      (node (ref "D31") (pin "2") (pinfunction "A_2") (pintype "passive"))
      (node (ref "D34") (pin "2") (pinfunction "A_2") (pintype "passive"))
      (node (ref "D37") (pin "2") (pinfunction "A_2") (pintype "passive"))
      (node (ref "D4") (pin "2") (pinfunction "A_2") (pintype "passive"))
      (node (ref "D40") (pin "2") (pinfunction "A_2") (pintype "passive"))
      (node (ref "D43") (pin "2") (pinfunction "A_2") (pintype "passive"))
      (node (ref "D46") (pin "2") (pinfunction "A_2") (pintype "passive"))
      (node (ref "D49") (pin "2") (pinfunction "A_2") (pintype "passive"))
      (node (ref "D52") (pin "2") (pinfunction "A_2") (pintype "passive"))
      (node (ref "D7") (pin "2") (pinfunction "A_2") (pintype "passive"))
      (node (ref "ST1") (pin "1") (pinfunction "1_1") (pintype "passive"))
      (node (ref "VS1") (pin "3") (pintype "passive"))
      (node (ref "VS10") (pin "3") (pintype "passive"))
      (node (ref "VS13") (pin "3") (pintype "passive"))
      (node (ref "VS16") (pin "3") (pintype "passive"))
      (node (ref "VS19") (pin "3") (pintype "passive"))
      (node (ref "VS22") (pin "3") (pintype "passive"))
      (node (ref "VS25") (pin "3") (pintype "passive"))
      (node (ref "VS28") (pin "3") (pintype "passive"))
      (node (ref "VS31") (pin "3") (pintype "passive"))
      (node (ref "VS34") (pin "3") (pintype "passive"))
      (node (ref "VS37") (pin "3") (pintype "passive"))
      (node (ref "VS4") (pin "3") (pintype "passive"))
      (node (ref "VS40") (pin "3") (pintype "passive"))
      (node (ref "VS43") (pin "3") (pintype "passive"))
      (node (ref "VS46") (pin "3") (pintype "passive"))
      (node (ref "VS49") (pin "3") (pintype "passive"))
      (node (ref "VS52") (pin "3") (pintype "passive"))
      (node (ref "VS7") (pin "3") (pintype "passive"))
    )
    (net (code "2") (name "/+U2") (class "Default")
      (node (ref "D100") (pin "2") (pinfunction "A_2") (pintype "passive"))
      (node (ref "D103") (pin "2") (pinfunction "A_2") (pintype "passive"))
      (node (ref "D106") (pin "2") (pinfunction "A_2") (pintype "passive"))
      (node (ref "D109") (pin "2") (pinfunction "A_2") (pintype "passive"))
      (node (ref "D55") (pin "2") (pinfunction "A_2") (pintype "passive"))
      (node (ref "D58") (pin "2") (pinfunction "A_2") (pintype "passive"))
      (node (ref "D61") (pin "2") (pinfunction "A_2") (pintype "passive"))
      (node (ref "D64") (pin "2") (pinfunction "A_2") (pintype "passive"))
      (node (ref "D67") (pin "2") (pinfunction "A_2") (pintype "passive"))
      (node (ref "D70") (pin "2") (pinfunction "A_2") (pintype "passive"))
      (node (ref "D73") (pin "2") (pinfunction "A_2") (pintype "passive"))
      (node (ref "D76") (pin "2") (pinfunction "A_2") (pintype "passive"))
      (node (ref "D79") (pin "2") (pinfunction "A_2") (pintype "passive"))
      (node (ref "D82") (pin "2") (pinfunction "A_2") (pintype "passive"))
      (node (ref "D85") (pin "2") (pinfunction "A_2") (pintype "passive"))
      (node (ref "D88") (pin "2") (pinfunction "A_2") (pintype "passive"))
      (node (ref "D91") (pin "2") (pinfunction "A_2") (pintype "passive"))
      (node (ref "D94") (pin "2") (pinfunction "A_2") (pintype "passive"))
      (node (ref "D97") (pin "2") (pinfunction "A_2") (pintype "passive"))
      (node (ref "ST1") (pin "2") (pinfunction "2_2") (pintype "passive"))
      (node (ref "VS100") (pin "3") (pintype "passive"))
      (node (ref "VS103") (pin "3") (pintype "passive"))
      (node (ref "VS106") (pin "3") (pintype "passive"))
      (node (ref "VS109") (pin "3") (pintype "passive"))
      (node (ref "VS55") (pin "3") (pintype "passive"))
      (node (ref "VS58") (pin "3") (pintype "passive"))
      (node (ref "VS61") (pin "3") (pintype "passive"))
      (node (ref "VS64") (pin "3") (pintype "passive"))
      (node (ref "VS67") (pin "3") (pintype "passive"))
      (node (ref "VS70") (pin "3") (pintype "passive"))
      (node (ref "VS73") (pin "3") (pintype "passive"))
      (node (ref "VS76") (pin "3") (pintype "passive"))
      (node (ref "VS79") (pin "3") (pintype "passive"))
      (node (ref "VS82") (pin "3") (pintype "passive"))
      (node (ref "VS85") (pin "3") (pintype "passive"))
      (node (ref "VS88") (pin "3") (pintype "passive"))
      (node (ref "VS91") (pin "3") (pintype "passive"))
      (node (ref "VS94") (pin "3") (pintype "passive"))
      (node (ref "VS97") (pin "3") (pintype "passive"))
    )
    (net (code "3") (name "/-U1") (class "Default")
      (node (ref "R1") (pin "2") (pinfunction "2_2") (pintype "passive"))
      (node (ref "R10") (pin "2") (pinfunction "2_2") (pintype "passive"))
      (node (ref "R11") (pin "2") (pinfunction "2_2") (pintype "passive"))
      (node (ref "R12") (pin "2") (pinfunction "2_2") (pintype "passive"))
      (node (ref "R13") (pin "2") (pinfunction "2_2") (pintype "passive"))
      (node (ref "R14") (pin "2") (pinfunction "2_2") (pintype "passive"))
      (node (ref "R15") (pin "2") (pinfunction "2_2") (pintype "passive"))
      (node (ref "R16") (pin "2") (pinfunction "2_2") (pintype "passive"))
      (node (ref "R17") (pin "2") (pinfunction "2_2") (pintype "passive"))
      (node (ref "R18") (pin "2") (pinfunction "2_2") (pintype "passive"))
      (node (ref "R2") (pin "2") (pinfunction "2_2") (pintype "passive"))
      (node (ref "R3") (pin "2") (pinfunction "2_2") (pintype "passive"))
      (node (ref "R4") (pin "2") (pinfunction "2_2") (pintype "passive"))
      (node (ref "R5") (pin "2") (pinfunction "2_2") (pintype "passive"))
      (node (ref "R6") (pin "2") (pinfunction "2_2") (pintype "passive"))
      (node (ref "R7") (pin "2") (pinfunction "2_2") (pintype "passive"))
      (node (ref "R8") (pin "2") (pinfunction "2_2") (pintype "passive"))
      (node (ref "R9") (pin "2") (pinfunction "2_2") (pintype "passive"))
      (node (ref "ST1") (pin "3") (pinfunction "3_3") (pintype "passive"))
    )
    (net (code "4") (name "/-U2") (class "Default")
      (node (ref "R19") (pin "2") (pinfunction "2_2") (pintype "passive"))
      (node (ref "R20") (pin "2") (pinfunction "2_2") (pintype "passive"))
      (node (ref "R21") (pin "2") (pinfunction "2_2") (pintype "passive"))
      (node (ref "R22") (pin "2") (pinfunction "2_2") (pintype "passive"))
      (node (ref "R23") (pin "2") (pinfunction "2_2") (pintype "passive"))
      (node (ref "R24") (pin "2") (pinfunction "2_2") (pintype "passive"))
      (node (ref "R25") (pin "2") (pinfunction "2_2") (pintype "passive"))
      (node (ref "R26") (pin "2") (pinfunction "2_2") (pintype "passive"))
      (node (ref "R27") (pin "2") (pinfunction "2_2") (pintype "passive"))
      (node (ref "R28") (pin "2") (pinfunction "2_2") (pintype "passive"))
      (node (ref "R29") (pin "2") (pinfunction "2_2") (pintype "passive"))
      (node (ref "R30") (pin "2") (pinfunction "2_2") (pintype "passive"))
      (node (ref "R31") (pin "2") (pinfunction "2_2") (pintype "passive"))
      (node (ref "R32") (pin "2") (pinfunction "2_2") (pintype "passive"))
      (node (ref "R33") (pin "2") (pinfunction "2_2") (pintype "passive"))
      (node (ref "R34") (pin "2") (pinfunction "2_2") (pintype "passive"))
      (node (ref "R35") (pin "2") (pinfunction "2_2") (pintype "passive"))
      (node (ref "R36") (pin "2") (pinfunction "2_2") (pintype "passive"))
      (node (ref "R38") (pin "2") (pinfunction "2_2") (pintype "passive"))
      (node (ref "ST1") (pin "4") (pinfunction "4_4") (pintype "passive"))
    )
    (net (code "5") (name "Net-(D1-K)") (class "Default")
      (node (ref "D1") (pin "1") (pinfunction "K_1") (pintype "passive"))
      (node (ref "D2") (pin "2") (pinfunction "A_2") (pintype "passive"))
      (node (ref "VS1") (pin "1") (pintype "passive"))
      (node (ref "VS2") (pin "3") (pintype "passive"))
    )
    (net (code "6") (name "Net-(D2-K)") (class "Default")
      (node (ref "D2") (pin "1") (pinfunction "K_1") (pintype "passive"))
      (node (ref "D3") (pin "2") (pinfunction "A_2") (pintype "passive"))
      (node (ref "VS2") (pin "1") (pintype "passive"))
      (node (ref "VS3") (pin "3") (pintype "passive"))
    )
    (net (code "7") (name "Net-(D3-K)") (class "Default")
      (node (ref "D3") (pin "1") (pinfunction "K_1") (pintype "passive"))
      (node (ref "R1") (pin "1") (pinfunction "1_1") (pintype "passive"))
      (node (ref "VS3") (pin "1") (pintype "passive"))
    )
    (net (code "8") (name "Net-(D4-K)") (class "Default")
      (node (ref "D4") (pin "1") (pinfunction "K_1") (pintype "passive"))
      (node (ref "D5") (pin "2") (pinfunction "A_2") (pintype "passive"))
      (node (ref "VS4") (pin "1") (pintype "passive"))
      (node (ref "VS5") (pin "3") (pintype "passive"))
    )
    (net (code "9") (name "Net-(D5-K)") (class "Default")
      (node (ref "D5") (pin "1") (pinfunction "K_1") (pintype "passive"))
      (node (ref "D6") (pin "2") (pinfunction "A_2") (pintype "passive"))
      (node (ref "VS5") (pin "1") (pintype "passive"))
      (node (ref "VS6") (pin "3") (pintype "passive"))
    )
    (net (code "10") (name "Net-(D6-K)") (class "Default")
      (node (ref "D6") (pin "1") (pinfunction "K_1") (pintype "passive"))
      (node (ref "R2") (pin "1") (pinfunction "1_1") (pintype "passive"))
      (node (ref "VS6") (pin "1") (pintype "passive"))
    )
    (net (code "11") (name "Net-(D7-K)") (class "Default")
      (node (ref "D7") (pin "1") (pinfunction "K_1") (pintype "passive"))
      (node (ref "D8") (pin "2") (pinfunction "A_2") (pintype "passive"))
      (node (ref "VS7") (pin "1") (pintype "passive"))
      (node (ref "VS8") (pin "3") (pintype "passive"))
    )
    (net (code "12") (name "Net-(D8-K)") (class "Default")
      (node (ref "D8") (pin "1") (pinfunction "K_1") (pintype "passive"))
      (node (ref "D9") (pin "2") (pinfunction "A_2") (pintype "passive"))
      (node (ref "VS8") (pin "1") (pintype "passive"))
      (node (ref "VS9") (pin "3") (pintype "passive"))
    )
    (net (code "13") (name "Net-(D9-K)") (class "Default")
      (node (ref "D9") (pin "1") (pinfunction "K_1") (pintype "passive"))
      (node (ref "R3") (pin "1") (pinfunction "1_1") (pintype "passive"))
      (node (ref "VS9") (pin "1") (pintype "passive"))
    )
    (net (code "14") (name "Net-(D10-K)") (class "Default")
      (node (ref "D10") (pin "1") (pinfunction "K_1") (pintype "passive"))
      (node (ref "D11") (pin "2") (pinfunction "A_2") (pintype "passive"))
      (node (ref "VS10") (pin "1") (pintype "passive"))
      (node (ref "VS11") (pin "3") (pintype "passive"))
    )
    (net (code "15") (name "Net-(D11-K)") (class "Default")
      (node (ref "D11") (pin "1") (pinfunction "K_1") (pintype "passive"))
      (node (ref "D12") (pin "2") (pinfunction "A_2") (pintype "passive"))
      (node (ref "VS11") (pin "1") (pintype "passive"))
      (node (ref "VS12") (pin "3") (pintype "passive"))
    )
    (net (code "16") (name "Net-(D12-K)") (class "Default")
      (node (ref "D12") (pin "1") (pinfunction "K_1") (pintype "passive"))
      (node (ref "R4") (pin "1") (pinfunction "1_1") (pintype "passive"))
      (node (ref "VS12") (pin "1") (pintype "passive"))
    )
    (net (code "17") (name "Net-(D13-K)") (class "Default")
      (node (ref "D13") (pin "1") (pinfunction "K_1") (pintype "passive"))
      (node (ref "D14") (pin "2") (pinfunction "A_2") (pintype "passive"))
      (node (ref "VS13") (pin "1") (pintype "passive"))
      (node (ref "VS14") (pin "3") (pintype "passive"))
    )
    (net (code "18") (name "Net-(D14-K)") (class "Default")
      (node (ref "D14") (pin "1") (pinfunction "K_1") (pintype "passive"))
      (node (ref "D15") (pin "2") (pinfunction "A_2") (pintype "passive"))
      (node (ref "VS14") (pin "1") (pintype "passive"))
      (node (ref "VS15") (pin "3") (pintype "passive"))
    )
    (net (code "19") (name "Net-(D15-K)") (class "Default")
      (node (ref "D15") (pin "1") (pinfunction "K_1") (pintype "passive"))
      (node (ref "R5") (pin "1") (pinfunction "1_1") (pintype "passive"))
      (node (ref "VS15") (pin "1") (pintype "passive"))
    )
    (net (code "20") (name "Net-(D16-K)") (class "Default")
      (node (ref "D16") (pin "1") (pinfunction "K_1") (pintype "passive"))
      (node (ref "D17") (pin "2") (pinfunction "A_2") (pintype "passive"))
      (node (ref "VS16") (pin "1") (pintype "passive"))
      (node (ref "VS17") (pin "3") (pintype "passive"))
    )
    (net (code "21") (name "Net-(D17-K)") (class "Default")
      (node (ref "D17") (pin "1") (pinfunction "K_1") (pintype "passive"))
      (node (ref "D18") (pin "2") (pinfunction "A_2") (pintype "passive"))
      (node (ref "VS17") (pin "1") (pintype "passive"))
      (node (ref "VS18") (pin "3") (pintype "passive"))
    )
    (net (code "22") (name "Net-(D18-K)") (class "Default")
      (node (ref "D18") (pin "1") (pinfunction "K_1") (pintype "passive"))
      (node (ref "R6") (pin "1") (pinfunction "1_1") (pintype "passive"))
      (node (ref "VS18") (pin "1") (pintype "passive"))
    )
    (net (code "23") (name "Net-(D19-K)") (class "Default")
      (node (ref "D19") (pin "1") (pinfunction "K_1") (pintype "passive"))
      (node (ref "D20") (pin "2") (pinfunction "A_2") (pintype "passive"))
      (node (ref "VS19") (pin "1") (pintype "passive"))
      (node (ref "VS20") (pin "3") (pintype "passive"))
    )
    (net (code "24") (name "Net-(D20-K)") (class "Default")
      (node (ref "D20") (pin "1") (pinfunction "K_1") (pintype "passive"))
      (node (ref "D21") (pin "2") (pinfunction "A_2") (pintype "passive"))
      (node (ref "VS20") (pin "1") (pintype "passive"))
      (node (ref "VS21") (pin "3") (pintype "passive"))
    )
    (net (code "25") (name "Net-(D21-K)") (class "Default")
      (node (ref "D21") (pin "1") (pinfunction "K_1") (pintype "passive"))
      (node (ref "R7") (pin "1") (pinfunction "1_1") (pintype "passive"))
      (node (ref "VS21") (pin "1") (pintype "passive"))
    )
    (net (code "26") (name "Net-(D22-K)") (class "Default")
      (node (ref "D22") (pin "1") (pinfunction "K_1") (pintype "passive"))
      (node (ref "D23") (pin "2") (pinfunction "A_2") (pintype "passive"))
      (node (ref "VS22") (pin "1") (pintype "passive"))
      (node (ref "VS23") (pin "3") (pintype "passive"))
    )
    (net (code "27") (name "Net-(D23-K)") (class "Default")
      (node (ref "D23") (pin "1") (pinfunction "K_1") (pintype "passive"))
      (node (ref "D24") (pin "2") (pinfunction "A_2") (pintype "passive"))
      (node (ref "VS23") (pin "1") (pintype "passive"))
      (node (ref "VS24") (pin "3") (pintype "passive"))
    )
    (net (code "28") (name "Net-(D24-K)") (class "Default")
      (node (ref "D24") (pin "1") (pinfunction "K_1") (pintype "passive"))
      (node (ref "R8") (pin "1") (pinfunction "1_1") (pintype "passive"))
      (node (ref "VS24") (pin "1") (pintype "passive"))
    )
    (net (code "29") (name "Net-(D25-K)") (class "Default")
      (node (ref "D25") (pin "1") (pinfunction "K_1") (pintype "passive"))
      (node (ref "D26") (pin "2") (pinfunction "A_2") (pintype "passive"))
      (node (ref "VS25") (pin "1") (pintype "passive"))
      (node (ref "VS26") (pin "3") (pintype "passive"))
    )
    (net (code "30") (name "Net-(D26-K)") (class "Default")
      (node (ref "D26") (pin "1") (pinfunction "K_1") (pintype "passive"))
      (node (ref "D27") (pin "2") (pinfunction "A_2") (pintype "passive"))
      (node (ref "VS26") (pin "1") (pintype "passive"))
      (node (ref "VS27") (pin "3") (pintype "passive"))
    )
    (net (code "31") (name "Net-(D27-K)") (class "Default")
      (node (ref "D27") (pin "1") (pinfunction "K_1") (pintype "passive"))
      (node (ref "R9") (pin "1") (pinfunction "1_1") (pintype "passive"))
      (node (ref "VS27") (pin "1") (pintype "passive"))
    )
    (net (code "32") (name "Net-(D28-K)") (class "Default")
      (node (ref "D28") (pin "1") (pinfunction "K_1") (pintype "passive"))
      (node (ref "D29") (pin "2") (pinfunction "A_2") (pintype "passive"))
      (node (ref "VS28") (pin "1") (pintype "passive"))
      (node (ref "VS29") (pin "3") (pintype "passive"))
    )
    (net (code "33") (name "Net-(D29-K)") (class "Default")
      (node (ref "D29") (pin "1") (pinfunction "K_1") (pintype "passive"))
      (node (ref "D30") (pin "2") (pinfunction "A_2") (pintype "passive"))
      (node (ref "VS29") (pin "1") (pintype "passive"))
      (node (ref "VS30") (pin "3") (pintype "passive"))
    )
    (net (code "34") (name "Net-(D30-K)") (class "Default")
      (node (ref "D30") (pin "1") (pinfunction "K_1") (pintype "passive"))
      (node (ref "R10") (pin "1") (pinfunction "1_1") (pintype "passive"))
      (node (ref "VS30") (pin "1") (pintype "passive"))
    )
    (net (code "35") (name "Net-(D31-K)") (class "Default")
      (node (ref "D31") (pin "1") (pinfunction "K_1") (pintype "passive"))
      (node (ref "D32") (pin "2") (pinfunction "A_2") (pintype "passive"))
      (node (ref "VS31") (pin "1") (pintype "passive"))
      (node (ref "VS32") (pin "3") (pintype "passive"))
    )
    (net (code "36") (name "Net-(D32-K)") (class "Default")
      (node (ref "D32") (pin "1") (pinfunction "K_1") (pintype "passive"))
      (node (ref "D33") (pin "2") (pinfunction "A_2") (pintype "passive"))
      (node (ref "VS32") (pin "1") (pintype "passive"))
      (node (ref "VS33") (pin "3") (pintype "passive"))
    )
    (net (code "37") (name "Net-(D33-K)") (class "Default")
      (node (ref "D33") (pin "1") (pinfunction "K_1") (pintype "passive"))
      (node (ref "R11") (pin "1") (pinfunction "1_1") (pintype "passive"))
      (node (ref "VS33") (pin "1") (pintype "passive"))
    )
    (net (code "38") (name "Net-(D34-K)") (class "Default")
      (node (ref "D34") (pin "1") (pinfunction "K_1") (pintype "passive"))
      (node (ref "D35") (pin "2") (pinfunction "A_2") (pintype "passive"))
      (node (ref "VS34") (pin "1") (pintype "passive"))
      (node (ref "VS35") (pin "3") (pintype "passive"))
    )
    (net (code "39") (name "Net-(D35-K)") (class "Default")
      (node (ref "D35") (pin "1") (pinfunction "K_1") (pintype "passive"))
      (node (ref "D36") (pin "2") (pinfunction "A_2") (pintype "passive"))
      (node (ref "VS35") (pin "1") (pintype "passive"))
      (node (ref "VS36") (pin "3") (pintype "passive"))
    )
    (net (code "40") (name "Net-(D36-K)") (class "Default")
      (node (ref "D36") (pin "1") (pinfunction "K_1") (pintype "passive"))
      (node (ref "R12") (pin "1") (pinfunction "1_1") (pintype "passive"))
      (node (ref "VS36") (pin "1") (pintype "passive"))
    )
    (net (code "41") (name "Net-(D37-K)") (class "Default")
      (node (ref "D37") (pin "1") (pinfunction "K_1") (pintype "passive"))
      (node (ref "D38") (pin "2") (pinfunction "A_2") (pintype "passive"))
      (node (ref "VS37") (pin "1") (pintype "passive"))
      (node (ref "VS38") (pin "3") (pintype "passive"))
    )
    (net (code "42") (name "Net-(D38-K)") (class "Default")
      (node (ref "D38") (pin "1") (pinfunction "K_1") (pintype "passive"))
      (node (ref "D39") (pin "2") (pinfunction "A_2") (pintype "passive"))
      (node (ref "VS38") (pin "1") (pintype "passive"))
      (node (ref "VS39") (pin "3") (pintype "passive"))
    )
    (net (code "43") (name "Net-(D39-K)") (class "Default")
      (node (ref "D39") (pin "1") (pinfunction "K_1") (pintype "passive"))
      (node (ref "R13") (pin "1") (pinfunction "1_1") (pintype "passive"))
      (node (ref "VS39") (pin "1") (pintype "passive"))
    )
    (net (code "44") (name "Net-(D40-K)") (class "Default")
      (node (ref "D40") (pin "1") (pinfunction "K_1") (pintype "passive"))
      (node (ref "D41") (pin "2") (pinfunction "A_2") (pintype "passive"))
      (node (ref "VS40") (pin "1") (pintype "passive"))
      (node (ref "VS41") (pin "3") (pintype "passive"))
    )
    (net (code "45") (name "Net-(D41-K)") (class "Default")
      (node (ref "D41") (pin "1") (pinfunction "K_1") (pintype "passive"))
      (node (ref "D42") (pin "2") (pinfunction "A_2") (pintype "passive"))
      (node (ref "VS41") (pin "1") (pintype "passive"))
      (node (ref "VS42") (pin "3") (pintype "passive"))
    )
    (net (code "46") (name "Net-(D42-K)") (class "Default")
      (node (ref "D42") (pin "1") (pinfunction "K_1") (pintype "passive"))
      (node (ref "R14") (pin "1") (pinfunction "1_1") (pintype "passive"))
      (node (ref "VS42") (pin "1") (pintype "passive"))
    )
    (net (code "47") (name "Net-(D43-K)") (class "Default")
      (node (ref "D43") (pin "1") (pinfunction "K_1") (pintype "passive"))
      (node (ref "D44") (pin "2") (pinfunction "A_2") (pintype "passive"))
      (node (ref "VS43") (pin "1") (pintype "passive"))
      (node (ref "VS44") (pin "3") (pintype "passive"))
    )
    (net (code "48") (name "Net-(D44-K)") (class "Default")
      (node (ref "D44") (pin "1") (pinfunction "K_1") (pintype "passive"))
      (node (ref "D45") (pin "2") (pinfunction "A_2") (pintype "passive"))
      (node (ref "VS44") (pin "1") (pintype "passive"))
      (node (ref "VS45") (pin "3") (pintype "passive"))
    )
    (net (code "49") (name "Net-(D45-K)") (class "Default")
      (node (ref "D45") (pin "1") (pinfunction "K_1") (pintype "passive"))
      (node (ref "R15") (pin "1") (pinfunction "1_1") (pintype "passive"))
      (node (ref "VS45") (pin "1") (pintype "passive"))
    )
    (net (code "50") (name "Net-(D46-K)") (class "Default")
      (node (ref "D46") (pin "1") (pinfunction "K_1") (pintype "passive"))
      (node (ref "D47") (pin "2") (pinfunction "A_2") (pintype "passive"))
      (node (ref "VS46") (pin "1") (pintype "passive"))
      (node (ref "VS47") (pin "3") (pintype "passive"))
    )
    (net (code "51") (name "Net-(D47-K)") (class "Default")
      (node (ref "D47") (pin "1") (pinfunction "K_1") (pintype "passive"))
      (node (ref "D48") (pin "2") (pinfunction "A_2") (pintype "passive"))
      (node (ref "VS47") (pin "1") (pintype "passive"))
      (node (ref "VS48") (pin "3") (pintype "passive"))
    )
    (net (code "52") (name "Net-(D48-K)") (class "Default")
      (node (ref "D48") (pin "1") (pinfunction "K_1") (pintype "passive"))
      (node (ref "R16") (pin "1") (pinfunction "1_1") (pintype "passive"))
      (node (ref "VS48") (pin "1") (pintype "passive"))
    )
    (net (code "53") (name "Net-(D49-K)") (class "Default")
      (node (ref "D49") (pin "1") (pinfunction "K_1") (pintype "passive"))
      (node (ref "D50") (pin "2") (pinfunction "A_2") (pintype "passive"))
      (node (ref "VS49") (pin "1") (pintype "passive"))
      (node (ref "VS50") (pin "3") (pintype "passive"))
    )
    (net (code "54") (name "Net-(D50-K)") (class "Default")
      (node (ref "D50") (pin "1") (pinfunction "K_1") (pintype "passive"))
      (node (ref "D51") (pin "2") (pinfunction "A_2") (pintype "passive"))
      (node (ref "VS50") (pin "1") (pintype "passive"))
      (node (ref "VS51") (pin "3") (pintype "passive"))
    )
    (net (code "55") (name "Net-(D51-K)") (class "Default")
      (node (ref "D51") (pin "1") (pinfunction "K_1") (pintype "passive"))
      (node (ref "R17") (pin "1") (pinfunction "1_1") (pintype "passive"))
      (node (ref "VS51") (pin "1") (pintype "passive"))
    )
    (net (code "56") (name "Net-(D52-K)") (class "Default")
      (node (ref "D52") (pin "1") (pinfunction "K_1") (pintype "passive"))
      (node (ref "D53") (pin "2") (pinfunction "A_2") (pintype "passive"))
      (node (ref "VS52") (pin "1") (pintype "passive"))
      (node (ref "VS53") (pin "3") (pintype "passive"))
    )
    (net (code "57") (name "Net-(D53-K)") (class "Default")
      (node (ref "D53") (pin "1") (pinfunction "K_1") (pintype "passive"))
      (node (ref "D54") (pin "2") (pinfunction "A_2") (pintype "passive"))
      (node (ref "VS53") (pin "1") (pintype "passive"))
      (node (ref "VS54") (pin "3") (pintype "passive"))
    )
    (net (code "58") (name "Net-(D54-K)") (class "Default")
      (node (ref "D54") (pin "1") (pinfunction "K_1") (pintype "passive"))
      (node (ref "R18") (pin "1") (pinfunction "1_1") (pintype "passive"))
      (node (ref "VS54") (pin "1") (pintype "passive"))
    )
    (net (code "59") (name "Net-(D55-K)") (class "Default")
      (node (ref "D55") (pin "1") (pinfunction "K_1") (pintype "passive"))
      (node (ref "D56") (pin "2") (pinfunction "A_2") (pintype "passive"))
      (node (ref "VS55") (pin "1") (pintype "passive"))
      (node (ref "VS56") (pin "3") (pintype "passive"))
    )
    (net (code "60") (name "Net-(D56-K)") (class "Default")
      (node (ref "D56") (pin "1") (pinfunction "K_1") (pintype "passive"))
      (node (ref "D57") (pin "2") (pinfunction "A_2") (pintype "passive"))
      (node (ref "VS56") (pin "1") (pintype "passive"))
      (node (ref "VS57") (pin "3") (pintype "passive"))
    )
    (net (code "61") (name "Net-(D57-K)") (class "Default")
      (node (ref "D57") (pin "1") (pinfunction "K_1") (pintype "passive"))
      (node (ref "R19") (pin "1") (pinfunction "1_1") (pintype "passive"))
      (node (ref "VS57") (pin "1") (pintype "passive"))
    )
    (net (code "62") (name "Net-(D58-K)") (class "Default")
      (node (ref "D58") (pin "1") (pinfunction "K_1") (pintype "passive"))
      (node (ref "D59") (pin "2") (pinfunction "A_2") (pintype "passive"))
      (node (ref "VS58") (pin "1") (pintype "passive"))
      (node (ref "VS59") (pin "3") (pintype "passive"))
    )
    (net (code "63") (name "Net-(D59-K)") (class "Default")
      (node (ref "D59") (pin "1") (pinfunction "K_1") (pintype "passive"))
      (node (ref "D60") (pin "2") (pinfunction "A_2") (pintype "passive"))
      (node (ref "VS59") (pin "1") (pintype "passive"))
      (node (ref "VS60") (pin "3") (pintype "passive"))
    )
    (net (code "64") (name "Net-(D60-K)") (class "Default")
      (node (ref "D60") (pin "1") (pinfunction "K_1") (pintype "passive"))
      (node (ref "R20") (pin "1") (pinfunction "1_1") (pintype "passive"))
      (node (ref "VS60") (pin "1") (pintype "passive"))
    )
    (net (code "65") (name "Net-(D61-K)") (class "Default")
      (node (ref "D61") (pin "1") (pinfunction "K_1") (pintype "passive"))
      (node (ref "D62") (pin "2") (pinfunction "A_2") (pintype "passive"))
      (node (ref "VS61") (pin "1") (pintype "passive"))
      (node (ref "VS62") (pin "3") (pintype "passive"))
    )
    (net (code "66") (name "Net-(D62-K)") (class "Default")
      (node (ref "D62") (pin "1") (pinfunction "K_1") (pintype "passive"))
      (node (ref "D63") (pin "2") (pinfunction "A_2") (pintype "passive"))
      (node (ref "VS62") (pin "1") (pintype "passive"))
      (node (ref "VS63") (pin "3") (pintype "passive"))
    )
    (net (code "67") (name "Net-(D63-K)") (class "Default")
      (node (ref "D63") (pin "1") (pinfunction "K_1") (pintype "passive"))
      (node (ref "R21") (pin "1") (pinfunction "1_1") (pintype "passive"))
      (node (ref "VS63") (pin "1") (pintype "passive"))
    )
    (net (code "68") (name "Net-(D64-K)") (class "Default")
      (node (ref "D64") (pin "1") (pinfunction "K_1") (pintype "passive"))
      (node (ref "D65") (pin "2") (pinfunction "A_2") (pintype "passive"))
      (node (ref "VS64") (pin "1") (pintype "passive"))
      (node (ref "VS65") (pin "3") (pintype "passive"))
    )
    (net (code "69") (name "Net-(D65-K)") (class "Default")
      (node (ref "D65") (pin "1") (pinfunction "K_1") (pintype "passive"))
      (node (ref "D66") (pin "2") (pinfunction "A_2") (pintype "passive"))
      (node (ref "VS65") (pin "1") (pintype "passive"))
      (node (ref "VS66") (pin "3") (pintype "passive"))
    )
    (net (code "70") (name "Net-(D66-K)") (class "Default")
      (node (ref "D66") (pin "1") (pinfunction "K_1") (pintype "passive"))
      (node (ref "R22") (pin "1") (pinfunction "1_1") (pintype "passive"))
      (node (ref "VS66") (pin "1") (pintype "passive"))
    )
    (net (code "71") (name "Net-(D67-K)") (class "Default")
      (node (ref "D67") (pin "1") (pinfunction "K_1") (pintype "passive"))
      (node (ref "D68") (pin "2") (pinfunction "A_2") (pintype "passive"))
      (node (ref "VS67") (pin "1") (pintype "passive"))
      (node (ref "VS68") (pin "3") (pintype "passive"))
    )
    (net (code "72") (name "Net-(D68-K)") (class "Default")
      (node (ref "D68") (pin "1") (pinfunction "K_1") (pintype "passive"))
      (node (ref "D69") (pin "2") (pinfunction "A_2") (pintype "passive"))
      (node (ref "VS68") (pin "1") (pintype "passive"))
      (node (ref "VS69") (pin "3") (pintype "passive"))
    )
    (net (code "73") (name "Net-(D69-K)") (class "Default")
      (node (ref "D69") (pin "1") (pinfunction "K_1") (pintype "passive"))
      (node (ref "R23") (pin "1") (pinfunction "1_1") (pintype "passive"))
      (node (ref "VS69") (pin "1") (pintype "passive"))
    )
    (net (code "74") (name "Net-(D70-K)") (class "Default")
      (node (ref "D70") (pin "1") (pinfunction "K_1") (pintype "passive"))
      (node (ref "D71") (pin "2") (pinfunction "A_2") (pintype "passive"))
      (node (ref "VS70") (pin "1") (pintype "passive"))
      (node (ref "VS71") (pin "3") (pintype "passive"))
    )
    (net (code "75") (name "Net-(D71-K)") (class "Default")
      (node (ref "D71") (pin "1") (pinfunction "K_1") (pintype "passive"))
      (node (ref "D72") (pin "2") (pinfunction "A_2") (pintype "passive"))
      (node (ref "VS71") (pin "1") (pintype "passive"))
      (node (ref "VS72") (pin "3") (pintype "passive"))
    )
    (net (code "76") (name "Net-(D72-K)") (class "Default")
      (node (ref "D72") (pin "1") (pinfunction "K_1") (pintype "passive"))
      (node (ref "R24") (pin "1") (pinfunction "1_1") (pintype "passive"))
      (node (ref "VS72") (pin "1") (pintype "passive"))
    )
    (net (code "77") (name "Net-(D73-K)") (class "Default")
      (node (ref "D73") (pin "1") (pinfunction "K_1") (pintype "passive"))
      (node (ref "D74") (pin "2") (pinfunction "A_2") (pintype "passive"))
      (node (ref "VS73") (pin "1") (pintype "passive"))
      (node (ref "VS74") (pin "3") (pintype "passive"))
    )
    (net (code "78") (name "Net-(D74-K)") (class "Default")
      (node (ref "D74") (pin "1") (pinfunction "K_1") (pintype "passive"))
      (node (ref "D75") (pin "2") (pinfunction "A_2") (pintype "passive"))
      (node (ref "VS74") (pin "1") (pintype "passive"))
      (node (ref "VS75") (pin "3") (pintype "passive"))
    )
    (net (code "79") (name "Net-(D75-K)") (class "Default")
      (node (ref "D75") (pin "1") (pinfunction "K_1") (pintype "passive"))
      (node (ref "R25") (pin "1") (pinfunction "1_1") (pintype "passive"))
      (node (ref "VS75") (pin "1") (pintype "passive"))
    )
    (net (code "80") (name "Net-(D76-K)") (class "Default")
      (node (ref "D76") (pin "1") (pinfunction "K_1") (pintype "passive"))
      (node (ref "D77") (pin "2") (pinfunction "A_2") (pintype "passive"))
      (node (ref "VS76") (pin "1") (pintype "passive"))
      (node (ref "VS77") (pin "3") (pintype "passive"))
    )
    (net (code "81") (name "Net-(D77-K)") (class "Default")
      (node (ref "D77") (pin "1") (pinfunction "K_1") (pintype "passive"))
      (node (ref "D78") (pin "2") (pinfunction "A_2") (pintype "passive"))
      (node (ref "VS77") (pin "1") (pintype "passive"))
      (node (ref "VS78") (pin "3") (pintype "passive"))
    )
    (net (code "82") (name "Net-(D78-K)") (class "Default")
      (node (ref "D78") (pin "1") (pinfunction "K_1") (pintype "passive"))
      (node (ref "R26") (pin "1") (pinfunction "1_1") (pintype "passive"))
      (node (ref "VS78") (pin "1") (pintype "passive"))
    )
    (net (code "83") (name "Net-(D79-K)") (class "Default")
      (node (ref "D79") (pin "1") (pinfunction "K_1") (pintype "passive"))
      (node (ref "D80") (pin "2") (pinfunction "A_2") (pintype "passive"))
      (node (ref "VS79") (pin "1") (pintype "passive"))
      (node (ref "VS80") (pin "3") (pintype "passive"))
    )
    (net (code "84") (name "Net-(D80-K)") (class "Default")
      (node (ref "D80") (pin "1") (pinfunction "K_1") (pintype "passive"))
      (node (ref "D81") (pin "2") (pinfunction "A_2") (pintype "passive"))
      (node (ref "VS80") (pin "1") (pintype "passive"))
      (node (ref "VS81") (pin "3") (pintype "passive"))
    )
    (net (code "85") (name "Net-(D81-K)") (class "Default")
      (node (ref "D81") (pin "1") (pinfunction "K_1") (pintype "passive"))
      (node (ref "R27") (pin "1") (pinfunction "1_1") (pintype "passive"))
      (node (ref "VS81") (pin "1") (pintype "passive"))
    )
    (net (code "86") (name "Net-(D82-K)") (class "Default")
      (node (ref "D82") (pin "1") (pinfunction "K_1") (pintype "passive"))
      (node (ref "D83") (pin "2") (pinfunction "A_2") (pintype "passive"))
      (node (ref "VS82") (pin "1") (pintype "passive"))
      (node (ref "VS83") (pin "3") (pintype "passive"))
    )
    (net (code "87") (name "Net-(D83-K)") (class "Default")
      (node (ref "D83") (pin "1") (pinfunction "K_1") (pintype "passive"))
      (node (ref "D84") (pin "2") (pinfunction "A_2") (pintype "passive"))
      (node (ref "VS83") (pin "1") (pintype "passive"))
      (node (ref "VS84") (pin "3") (pintype "passive"))
    )
    (net (code "88") (name "Net-(D84-K)") (class "Default")
      (node (ref "D84") (pin "1") (pinfunction "K_1") (pintype "passive"))
      (node (ref "R28") (pin "1") (pinfunction "1_1") (pintype "passive"))
      (node (ref "VS84") (pin "1") (pintype "passive"))
    )
    (net (code "89") (name "Net-(D85-K)") (class "Default")
      (node (ref "D85") (pin "1") (pinfunction "K_1") (pintype "passive"))
      (node (ref "D86") (pin "2") (pinfunction "A_2") (pintype "passive"))
      (node (ref "VS85") (pin "1") (pintype "passive"))
      (node (ref "VS86") (pin "3") (pintype "passive"))
    )
    (net (code "90") (name "Net-(D86-K)") (class "Default")
      (node (ref "D86") (pin "1") (pinfunction "K_1") (pintype "passive"))
      (node (ref "D87") (pin "2") (pinfunction "A_2") (pintype "passive"))
      (node (ref "VS86") (pin "1") (pintype "passive"))
      (node (ref "VS87") (pin "3") (pintype "passive"))
    )
    (net (code "91") (name "Net-(D87-K)") (class "Default")
      (node (ref "D87") (pin "1") (pinfunction "K_1") (pintype "passive"))
      (node (ref "R29") (pin "1") (pinfunction "1_1") (pintype "passive"))
      (node (ref "VS87") (pin "1") (pintype "passive"))
    )
    (net (code "92") (name "Net-(D88-K)") (class "Default")
      (node (ref "D88") (pin "1") (pinfunction "K_1") (pintype "passive"))
      (node (ref "D89") (pin "2") (pinfunction "A_2") (pintype "passive"))
      (node (ref "VS88") (pin "1") (pintype "passive"))
      (node (ref "VS89") (pin "3") (pintype "passive"))
    )
    (net (code "93") (name "Net-(D89-K)") (class "Default")
      (node (ref "D89") (pin "1") (pinfunction "K_1") (pintype "passive"))
      (node (ref "D90") (pin "2") (pinfunction "A_2") (pintype "passive"))
      (node (ref "VS89") (pin "1") (pintype "passive"))
      (node (ref "VS90") (pin "3") (pintype "passive"))
    )
    (net (code "94") (name "Net-(D90-K)") (class "Default")
      (node (ref "D90") (pin "1") (pinfunction "K_1") (pintype "passive"))
      (node (ref "R30") (pin "1") (pinfunction "1_1") (pintype "passive"))
      (node (ref "VS90") (pin "1") (pintype "passive"))
    )
    (net (code "95") (name "Net-(D91-K)") (class "Default")
      (node (ref "D91") (pin "1") (pinfunction "K_1") (pintype "passive"))
      (node (ref "D92") (pin "2") (pinfunction "A_2") (pintype "passive"))
      (node (ref "VS91") (pin "1") (pintype "passive"))
      (node (ref "VS92") (pin "3") (pintype "passive"))
    )
    (net (code "96") (name "Net-(D92-K)") (class "Default")
      (node (ref "D92") (pin "1") (pinfunction "K_1") (pintype "passive"))
      (node (ref "D93") (pin "2") (pinfunction "A_2") (pintype "passive"))
      (node (ref "VS92") (pin "1") (pintype "passive"))
      (node (ref "VS93") (pin "3") (pintype "passive"))
    )
    (net (code "97") (name "Net-(D93-K)") (class "Default")
      (node (ref "D93") (pin "1") (pinfunction "K_1") (pintype "passive"))
      (node (ref "R31") (pin "1") (pinfunction "1_1") (pintype "passive"))
      (node (ref "VS93") (pin "1") (pintype "passive"))
    )
    (net (code "98") (name "Net-(D94-K)") (class "Default")
      (node (ref "D94") (pin "1") (pinfunction "K_1") (pintype "passive"))
      (node (ref "D95") (pin "2") (pinfunction "A_2") (pintype "passive"))
      (node (ref "VS94") (pin "1") (pintype "passive"))
      (node (ref "VS95") (pin "3") (pintype "passive"))
    )
    (net (code "99") (name "Net-(D95-K)") (class "Default")
      (node (ref "D95") (pin "1") (pinfunction "K_1") (pintype "passive"))
      (node (ref "D96") (pin "2") (pinfunction "A_2") (pintype "passive"))
      (node (ref "VS95") (pin "1") (pintype "passive"))
      (node (ref "VS96") (pin "3") (pintype "passive"))
    )
    (net (code "100") (name "Net-(D96-K)") (class "Default")
      (node (ref "D96") (pin "1") (pinfunction "K_1") (pintype "passive"))
      (node (ref "R32") (pin "1") (pinfunction "1_1") (pintype "passive"))
      (node (ref "VS96") (pin "1") (pintype "passive"))
    )
    (net (code "101") (name "Net-(D97-K)") (class "Default")
      (node (ref "D97") (pin "1") (pinfunction "K_1") (pintype "passive"))
      (node (ref "D98") (pin "2") (pinfunction "A_2") (pintype "passive"))
      (node (ref "VS97") (pin "1") (pintype "passive"))
      (node (ref "VS98") (pin "3") (pintype "passive"))
    )
    (net (code "102") (name "Net-(D98-K)") (class "Default")
      (node (ref "D98") (pin "1") (pinfunction "K_1") (pintype "passive"))
      (node (ref "D99") (pin "2") (pinfunction "A_2") (pintype "passive"))
      (node (ref "VS98") (pin "1") (pintype "passive"))
      (node (ref "VS99") (pin "3") (pintype "passive"))
    )
    (net (code "103") (name "Net-(D99-K)") (class "Default")
      (node (ref "D99") (pin "1") (pinfunction "K_1") (pintype "passive"))
      (node (ref "R33") (pin "1") (pinfunction "1_1") (pintype "passive"))
      (node (ref "VS99") (pin "1") (pintype "passive"))
    )
    (net (code "104") (name "Net-(D100-K)") (class "Default")
      (node (ref "D100") (pin "1") (pinfunction "K_1") (pintype "passive"))
      (node (ref "D101") (pin "2") (pinfunction "A_2") (pintype "passive"))
      (node (ref "VS100") (pin "1") (pintype "passive"))
      (node (ref "VS101") (pin "3") (pintype "passive"))
    )
    (net (code "105") (name "Net-(D101-K)") (class "Default")
      (node (ref "D101") (pin "1") (pinfunction "K_1") (pintype "passive"))
      (node (ref "D102") (pin "2") (pinfunction "A_2") (pintype "passive"))
      (node (ref "VS101") (pin "1") (pintype "passive"))
      (node (ref "VS102") (pin "3") (pintype "passive"))
    )
    (net (code "106") (name "Net-(D102-K)") (class "Default")
      (node (ref "D102") (pin "1") (pinfunction "K_1") (pintype "passive"))
      (node (ref "R34") (pin "1") (pinfunction "1_1") (pintype "passive"))
      (node (ref "VS102") (pin "1") (pintype "passive"))
    )
    (net (code "107") (name "Net-(D103-K)") (class "Default")
      (node (ref "D103") (pin "1") (pinfunction "K_1") (pintype "passive"))
      (node (ref "D104") (pin "2") (pinfunction "A_2") (pintype "passive"))
      (node (ref "VS103") (pin "1") (pintype "passive"))
      (node (ref "VS104") (pin "3") (pintype "passive"))
    )
    (net (code "108") (name "Net-(D104-K)") (class "Default")
      (node (ref "D104") (pin "1") (pinfunction "K_1") (pintype "passive"))
      (node (ref "D105") (pin "2") (pinfunction "A_2") (pintype "passive"))
      (node (ref "VS104") (pin "1") (pintype "passive"))
      (node (ref "VS105") (pin "3") (pintype "passive"))
    )
    (net (code "109") (name "Net-(D105-K)") (class "Default")
      (node (ref "D105") (pin "1") (pinfunction "K_1") (pintype "passive"))
      (node (ref "R35") (pin "1") (pinfunction "1_1") (pintype "passive"))
      (node (ref "VS105") (pin "1") (pintype "passive"))
    )
    (net (code "110") (name "Net-(D106-K)") (class "Default")
      (node (ref "D106") (pin "1") (pinfunction "K_1") (pintype "passive"))
      (node (ref "D107") (pin "2") (pinfunction "A_2") (pintype "passive"))
      (node (ref "VS106") (pin "1") (pintype "passive"))
      (node (ref "VS107") (pin "3") (pintype "passive"))
    )
    (net (code "111") (name "Net-(D107-K)") (class "Default")
      (node (ref "D107") (pin "1") (pinfunction "K_1") (pintype "passive"))
      (node (ref "D108") (pin "2") (pinfunction "A_2") (pintype "passive"))
      (node (ref "VS107") (pin "1") (pintype "passive"))
      (node (ref "VS108") (pin "3") (pintype "passive"))
    )
    (net (code "112") (name "Net-(D108-K)") (class "Default")
      (node (ref "D108") (pin "1") (pinfunction "K_1") (pintype "passive"))
      (node (ref "R36") (pin "1") (pinfunction "1_1") (pintype "passive"))
      (node (ref "VS108") (pin "1") (pintype "passive"))
    )
    (net (code "113") (name "Net-(D109-K)") (class "Default")
      (node (ref "D109") (pin "1") (pinfunction "K_1") (pintype "passive"))
      (node (ref "D110") (pin "2") (pinfunction "A_2") (pintype "passive"))
      (node (ref "VS109") (pin "1") (pintype "passive"))
      (node (ref "VS110") (pin "3") (pintype "passive"))
    )
    (net (code "114") (name "Net-(D110-K)") (class "Default")
      (node (ref "D110") (pin "1") (pinfunction "K_1") (pintype "passive"))
      (node (ref "R37") (pin "1") (pinfunction "1_1") (pintype "passive"))
      (node (ref "VS110") (pin "1") (pintype "passive"))
    )
    (net (code "115") (name "Net-(R37-Pad2)") (class "Default")
      (node (ref "R37") (pin "2") (pinfunction "2_2") (pintype "passive"))
      (node (ref "R38") (pin "1") (pinfunction "1_1") (pintype "passive"))
    )
    (net (code "116") (name "unconnected-(ST1-Pad5)") (class "Default")
      (node (ref "ST1") (pin "5") (pintype "passive"))
    )
    (net (code "117") (name "unconnected-(ST1-Pad6)") (class "Default")
      (node (ref "ST1") (pin "6") (pintype "passive"))
    )
    (net (code "118") (name "unconnected-(ST1-Pad7)") (class "Default")
      (node (ref "ST1") (pin "7") (pintype "passive"))
    )
    (net (code "119") (name "unconnected-(ST1-Pad8)") (class "Default")
      (node (ref "ST1") (pin "8") (pintype "passive"))
    )
    (net (code "120") (name "unconnected-(VS1-Pad2)") (class "Default")
      (node (ref "VS1") (pin "2") (pintype "passive"))
    )
    (net (code "121") (name "unconnected-(VS2-Pad2)") (class "Default")
      (node (ref "VS2") (pin "2") (pintype "passive"))
    )
    (net (code "122") (name "unconnected-(VS3-Pad2)") (class "Default")
      (node (ref "VS3") (pin "2") (pintype "passive"))
    )
    (net (code "123") (name "unconnected-(VS4-Pad2)") (class "Default")
      (node (ref "VS4") (pin "2") (pintype "passive"))
    )
    (net (code "124") (name "unconnected-(VS5-Pad2)") (class "Default")
      (node (ref "VS5") (pin "2") (pintype "passive"))
    )
    (net (code "125") (name "unconnected-(VS6-Pad2)") (class "Default")
      (node (ref "VS6") (pin "2") (pintype "passive"))
    )
    (net (code "126") (name "unconnected-(VS7-Pad2)") (class "Default")
      (node (ref "VS7") (pin "2") (pintype "passive"))
    )
    (net (code "127") (name "unconnected-(VS8-Pad2)") (class "Default")
      (node (ref "VS8") (pin "2") (pintype "passive"))
    )
    (net (code "128") (name "unconnected-(VS9-Pad2)") (class "Default")
      (node (ref "VS9") (pin "2") (pintype "passive"))
    )
    (net (code "129") (name "unconnected-(VS10-Pad2)") (class "Default")
      (node (ref "VS10") (pin "2") (pintype "passive"))
    )
    (net (code "130") (name "unconnected-(VS11-Pad2)") (class "Default")
      (node (ref "VS11") (pin "2") (pintype "passive"))
    )
    (net (code "131") (name "unconnected-(VS12-Pad2)") (class "Default")
      (node (ref "VS12") (pin "2") (pintype "passive"))
    )
    (net (code "132") (name "unconnected-(VS13-Pad2)") (class "Default")
      (node (ref "VS13") (pin "2") (pintype "passive"))
    )
    (net (code "133") (name "unconnected-(VS14-Pad2)") (class "Default")
      (node (ref "VS14") (pin "2") (pintype "passive"))
    )
    (net (code "134") (name "unconnected-(VS15-Pad2)") (class "Default")
      (node (ref "VS15") (pin "2") (pintype "passive"))
    )
    (net (code "135") (name "unconnected-(VS16-Pad2)") (class "Default")
      (node (ref "VS16") (pin "2") (pintype "passive"))
    )
    (net (code "136") (name "unconnected-(VS17-Pad2)") (class "Default")
      (node (ref "VS17") (pin "2") (pintype "passive"))
    )
    (net (code "137") (name "unconnected-(VS18-Pad2)") (class "Default")
      (node (ref "VS18") (pin "2") (pintype "passive"))
    )
    (net (code "138") (name "unconnected-(VS19-Pad2)") (class "Default")
      (node (ref "VS19") (pin "2") (pintype "passive"))
    )
    (net (code "139") (name "unconnected-(VS20-Pad2)") (class "Default")
      (node (ref "VS20") (pin "2") (pintype "passive"))
    )
    (net (code "140") (name "unconnected-(VS21-Pad2)") (class "Default")
      (node (ref "VS21") (pin "2") (pintype "passive"))
    )
    (net (code "141") (name "unconnected-(VS22-Pad2)") (class "Default")
      (node (ref "VS22") (pin "2") (pintype "passive"))
    )
    (net (code "142") (name "unconnected-(VS23-Pad2)") (class "Default")
      (node (ref "VS23") (pin "2") (pintype "passive"))
    )
    (net (code "143") (name "unconnected-(VS24-Pad2)") (class "Default")
      (node (ref "VS24") (pin "2") (pintype "passive"))
    )
    (net (code "144") (name "unconnected-(VS25-Pad2)") (class "Default")
      (node (ref "VS25") (pin "2") (pintype "passive"))
    )
    (net (code "145") (name "unconnected-(VS26-Pad2)") (class "Default")
      (node (ref "VS26") (pin "2") (pintype "passive"))
    )
    (net (code "146") (name "unconnected-(VS27-Pad2)") (class "Default")
      (node (ref "VS27") (pin "2") (pintype "passive"))
    )
    (net (code "147") (name "unconnected-(VS28-Pad2)") (class "Default")
      (node (ref "VS28") (pin "2") (pintype "passive"))
    )
    (net (code "148") (name "unconnected-(VS29-Pad2)") (class "Default")
      (node (ref "VS29") (pin "2") (pintype "passive"))
    )
    (net (code "149") (name "unconnected-(VS30-Pad2)") (class "Default")
      (node (ref "VS30") (pin "2") (pintype "passive"))
    )
    (net (code "150") (name "unconnected-(VS31-Pad2)") (class "Default")
      (node (ref "VS31") (pin "2") (pintype "passive"))
    )
    (net (code "151") (name "unconnected-(VS32-Pad2)") (class "Default")
      (node (ref "VS32") (pin "2") (pintype "passive"))
    )
    (net (code "152") (name "unconnected-(VS33-Pad2)") (class "Default")
      (node (ref "VS33") (pin "2") (pintype "passive"))
    )
    (net (code "153") (name "unconnected-(VS34-Pad2)") (class "Default")
      (node (ref "VS34") (pin "2") (pintype "passive"))
    )
    (net (code "154") (name "unconnected-(VS35-Pad2)") (class "Default")
      (node (ref "VS35") (pin "2") (pintype "passive"))
    )
    (net (code "155") (name "unconnected-(VS36-Pad2)") (class "Default")
      (node (ref "VS36") (pin "2") (pintype "passive"))
    )
    (net (code "156") (name "unconnected-(VS37-Pad2)") (class "Default")
      (node (ref "VS37") (pin "2") (pintype "passive"))
    )
    (net (code "157") (name "unconnected-(VS38-Pad2)") (class "Default")
      (node (ref "VS38") (pin "2") (pintype "passive"))
    )
    (net (code "158") (name "unconnected-(VS39-Pad2)") (class "Default")
      (node (ref "VS39") (pin "2") (pintype "passive"))
    )
    (net (code "159") (name "unconnected-(VS40-Pad2)") (class "Default")
      (node (ref "VS40") (pin "2") (pintype "passive"))
    )
    (net (code "160") (name "unconnected-(VS41-Pad2)") (class "Default")
      (node (ref "VS41") (pin "2") (pintype "passive"))
    )
    (net (code "161") (name "unconnected-(VS42-Pad2)") (class "Default")
      (node (ref "VS42") (pin "2") (pintype "passive"))
    )
    (net (code "162") (name "unconnected-(VS43-Pad2)") (class "Default")
      (node (ref "VS43") (pin "2") (pintype "passive"))
    )
    (net (code "163") (name "unconnected-(VS44-Pad2)") (class "Default")
      (node (ref "VS44") (pin "2") (pintype "passive"))
    )
    (net (code "164") (name "unconnected-(VS45-Pad2)") (class "Default")
      (node (ref "VS45") (pin "2") (pintype "passive"))
    )
    (net (code "165") (name "unconnected-(VS46-Pad2)") (class "Default")
      (node (ref "VS46") (pin "2") (pintype "passive"))
    )
    (net (code "166") (name "unconnected-(VS47-Pad2)") (class "Default")
      (node (ref "VS47") (pin "2") (pintype "passive"))
    )
    (net (code "167") (name "unconnected-(VS48-Pad2)") (class "Default")
      (node (ref "VS48") (pin "2") (pintype "passive"))
    )
    (net (code "168") (name "unconnected-(VS49-Pad2)") (class "Default")
      (node (ref "VS49") (pin "2") (pintype "passive"))
    )
    (net (code "169") (name "unconnected-(VS50-Pad2)") (class "Default")
      (node (ref "VS50") (pin "2") (pintype "passive"))
    )
    (net (code "170") (name "unconnected-(VS51-Pad2)") (class "Default")
      (node (ref "VS51") (pin "2") (pintype "passive"))
    )
    (net (code "171") (name "unconnected-(VS52-Pad2)") (class "Default")
      (node (ref "VS52") (pin "2") (pintype "passive"))
    )
    (net (code "172") (name "unconnected-(VS53-Pad2)") (class "Default")
      (node (ref "VS53") (pin "2") (pintype "passive"))
    )
    (net (code "173") (name "unconnected-(VS54-Pad2)") (class "Default")
      (node (ref "VS54") (pin "2") (pintype "passive"))
    )
    (net (code "174") (name "unconnected-(VS55-Pad2)") (class "Default")
      (node (ref "VS55") (pin "2") (pintype "passive"))
    )
    (net (code "175") (name "unconnected-(VS56-Pad2)") (class "Default")
      (node (ref "VS56") (pin "2") (pintype "passive"))
    )
    (net (code "176") (name "unconnected-(VS57-Pad2)") (class "Default")
      (node (ref "VS57") (pin "2") (pintype "passive"))
    )
    (net (code "177") (name "unconnected-(VS58-Pad2)") (class "Default")
      (node (ref "VS58") (pin "2") (pintype "passive"))
    )
    (net (code "178") (name "unconnected-(VS59-Pad2)") (class "Default")
      (node (ref "VS59") (pin "2") (pintype "passive"))
    )
    (net (code "179") (name "unconnected-(VS60-Pad2)") (class "Default")
      (node (ref "VS60") (pin "2") (pintype "passive"))
    )
    (net (code "180") (name "unconnected-(VS61-Pad2)") (class "Default")
      (node (ref "VS61") (pin "2") (pintype "passive"))
    )
    (net (code "181") (name "unconnected-(VS62-Pad2)") (class "Default")
      (node (ref "VS62") (pin "2") (pintype "passive"))
    )
    (net (code "182") (name "unconnected-(VS63-Pad2)") (class "Default")
      (node (ref "VS63") (pin "2") (pintype "passive"))
    )
    (net (code "183") (name "unconnected-(VS64-Pad2)") (class "Default")
      (node (ref "VS64") (pin "2") (pintype "passive"))
    )
    (net (code "184") (name "unconnected-(VS65-Pad2)") (class "Default")
      (node (ref "VS65") (pin "2") (pintype "passive"))
    )
    (net (code "185") (name "unconnected-(VS66-Pad2)") (class "Default")
      (node (ref "VS66") (pin "2") (pintype "passive"))
    )
    (net (code "186") (name "unconnected-(VS67-Pad2)") (class "Default")
      (node (ref "VS67") (pin "2") (pintype "passive"))
    )
    (net (code "187") (name "unconnected-(VS68-Pad2)") (class "Default")
      (node (ref "VS68") (pin "2") (pintype "passive"))
    )
    (net (code "188") (name "unconnected-(VS69-Pad2)") (class "Default")
      (node (ref "VS69") (pin "2") (pintype "passive"))
    )
    (net (code "189") (name "unconnected-(VS70-Pad2)") (class "Default")
      (node (ref "VS70") (pin "2") (pintype "passive"))
    )
    (net (code "190") (name "unconnected-(VS71-Pad2)") (class "Default")
      (node (ref "VS71") (pin "2") (pintype "passive"))
    )
    (net (code "191") (name "unconnected-(VS72-Pad2)") (class "Default")
      (node (ref "VS72") (pin "2") (pintype "passive"))
    )
    (net (code "192") (name "unconnected-(VS73-Pad2)") (class "Default")
      (node (ref "VS73") (pin "2") (pintype "passive"))
    )
    (net (code "193") (name "unconnected-(VS74-Pad2)") (class "Default")
      (node (ref "VS74") (pin "2") (pintype "passive"))
    )
    (net (code "194") (name "unconnected-(VS75-Pad2)") (class "Default")
      (node (ref "VS75") (pin "2") (pintype "passive"))
    )
    (net (code "195") (name "unconnected-(VS76-Pad2)") (class "Default")
      (node (ref "VS76") (pin "2") (pintype "passive"))
    )
    (net (code "196") (name "unconnected-(VS77-Pad2)") (class "Default")
      (node (ref "VS77") (pin "2") (pintype "passive"))
    )
    (net (code "197") (name "unconnected-(VS78-Pad2)") (class "Default")
      (node (ref "VS78") (pin "2") (pintype "passive"))
    )
    (net (code "198") (name "unconnected-(VS79-Pad2)") (class "Default")
      (node (ref "VS79") (pin "2") (pintype "passive"))
    )
    (net (code "199") (name "unconnected-(VS80-Pad2)") (class "Default")
      (node (ref "VS80") (pin "2") (pintype "passive"))
    )
    (net (code "200") (name "unconnected-(VS81-Pad2)") (class "Default")
      (node (ref "VS81") (pin "2") (pintype "passive"))
    )
    (net (code "201") (name "unconnected-(VS82-Pad2)") (class "Default")
      (node (ref "VS82") (pin "2") (pintype "passive"))
    )
    (net (code "202") (name "unconnected-(VS83-Pad2)") (class "Default")
      (node (ref "VS83") (pin "2") (pintype "passive"))
    )
    (net (code "203") (name "unconnected-(VS84-Pad2)") (class "Default")
      (node (ref "VS84") (pin "2") (pintype "passive"))
    )
    (net (code "204") (name "unconnected-(VS85-Pad2)") (class "Default")
      (node (ref "VS85") (pin "2") (pintype "passive"))
    )
    (net (code "205") (name "unconnected-(VS86-Pad2)") (class "Default")
      (node (ref "VS86") (pin "2") (pintype "passive"))
    )
    (net (code "206") (name "unconnected-(VS87-Pad2)") (class "Default")
      (node (ref "VS87") (pin "2") (pintype "passive"))
    )
    (net (code "207") (name "unconnected-(VS88-Pad2)") (class "Default")
      (node (ref "VS88") (pin "2") (pintype "passive"))
    )
    (net (code "208") (name "unconnected-(VS89-Pad2)") (class "Default")
      (node (ref "VS89") (pin "2") (pintype "passive"))
    )
    (net (code "209") (name "unconnected-(VS90-Pad2)") (class "Default")
      (node (ref "VS90") (pin "2") (pintype "passive"))
    )
    (net (code "210") (name "unconnected-(VS91-Pad2)") (class "Default")
      (node (ref "VS91") (pin "2") (pintype "passive"))
    )
    (net (code "211") (name "unconnected-(VS92-Pad2)") (class "Default")
      (node (ref "VS92") (pin "2") (pintype "passive"))
    )
    (net (code "212") (name "unconnected-(VS93-Pad2)") (class "Default")
      (node (ref "VS93") (pin "2") (pintype "passive"))
    )
    (net (code "213") (name "unconnected-(VS94-Pad2)") (class "Default")
      (node (ref "VS94") (pin "2") (pintype "passive"))
    )
    (net (code "214") (name "unconnected-(VS95-Pad2)") (class "Default")
      (node (ref "VS95") (pin "2") (pintype "passive"))
    )
    (net (code "215") (name "unconnected-(VS96-Pad2)") (class "Default")
      (node (ref "VS96") (pin "2") (pintype "passive"))
    )
    (net (code "216") (name "unconnected-(VS97-Pad2)") (class "Default")
      (node (ref "VS97") (pin "2") (pintype "passive"))
    )
    (net (code "217") (name "unconnected-(VS98-Pad2)") (class "Default")
      (node (ref "VS98") (pin "2") (pintype "passive"))
    )
    (net (code "218") (name "unconnected-(VS99-Pad2)") (class "Default")
      (node (ref "VS99") (pin "2") (pintype "passive"))
    )
    (net (code "219") (name "unconnected-(VS100-Pad2)") (class "Default")
      (node (ref "VS100") (pin "2") (pintype "passive"))
    )
    (net (code "220") (name "unconnected-(VS101-Pad2)") (class "Default")
      (node (ref "VS101") (pin "2") (pintype "passive"))
    )
    (net (code "221") (name "unconnected-(VS102-Pad2)") (class "Default")
      (node (ref "VS102") (pin "2") (pintype "passive"))
    )
    (net (code "222") (name "unconnected-(VS103-Pad2)") (class "Default")
      (node (ref "VS103") (pin "2") (pintype "passive"))
    )
    (net (code "223") (name "unconnected-(VS104-Pad2)") (class "Default")
      (node (ref "VS104") (pin "2") (pintype "passive"))
    )
    (net (code "224") (name "unconnected-(VS105-Pad2)") (class "Default")
      (node (ref "VS105") (pin "2") (pintype "passive"))
    )
    (net (code "225") (name "unconnected-(VS106-Pad2)") (class "Default")
      (node (ref "VS106") (pin "2") (pintype "passive"))
    )
    (net (code "226") (name "unconnected-(VS107-Pad2)") (class "Default")
      (node (ref "VS107") (pin "2") (pintype "passive"))
    )
    (net (code "227") (name "unconnected-(VS108-Pad2)") (class "Default")
      (node (ref "VS108") (pin "2") (pintype "passive"))
    )
    (net (code "228") (name "unconnected-(VS109-Pad2)") (class "Default")
      (node (ref "VS109") (pin "2") (pintype "passive"))
    )
    (net (code "229") (name "unconnected-(VS110-Pad2)") (class "Default")
      (node (ref "VS110") (pin "2") (pintype "passive"))
    )
  )
)
